# das48.net
KiCad netlist of a schematic drawn in EAGLE
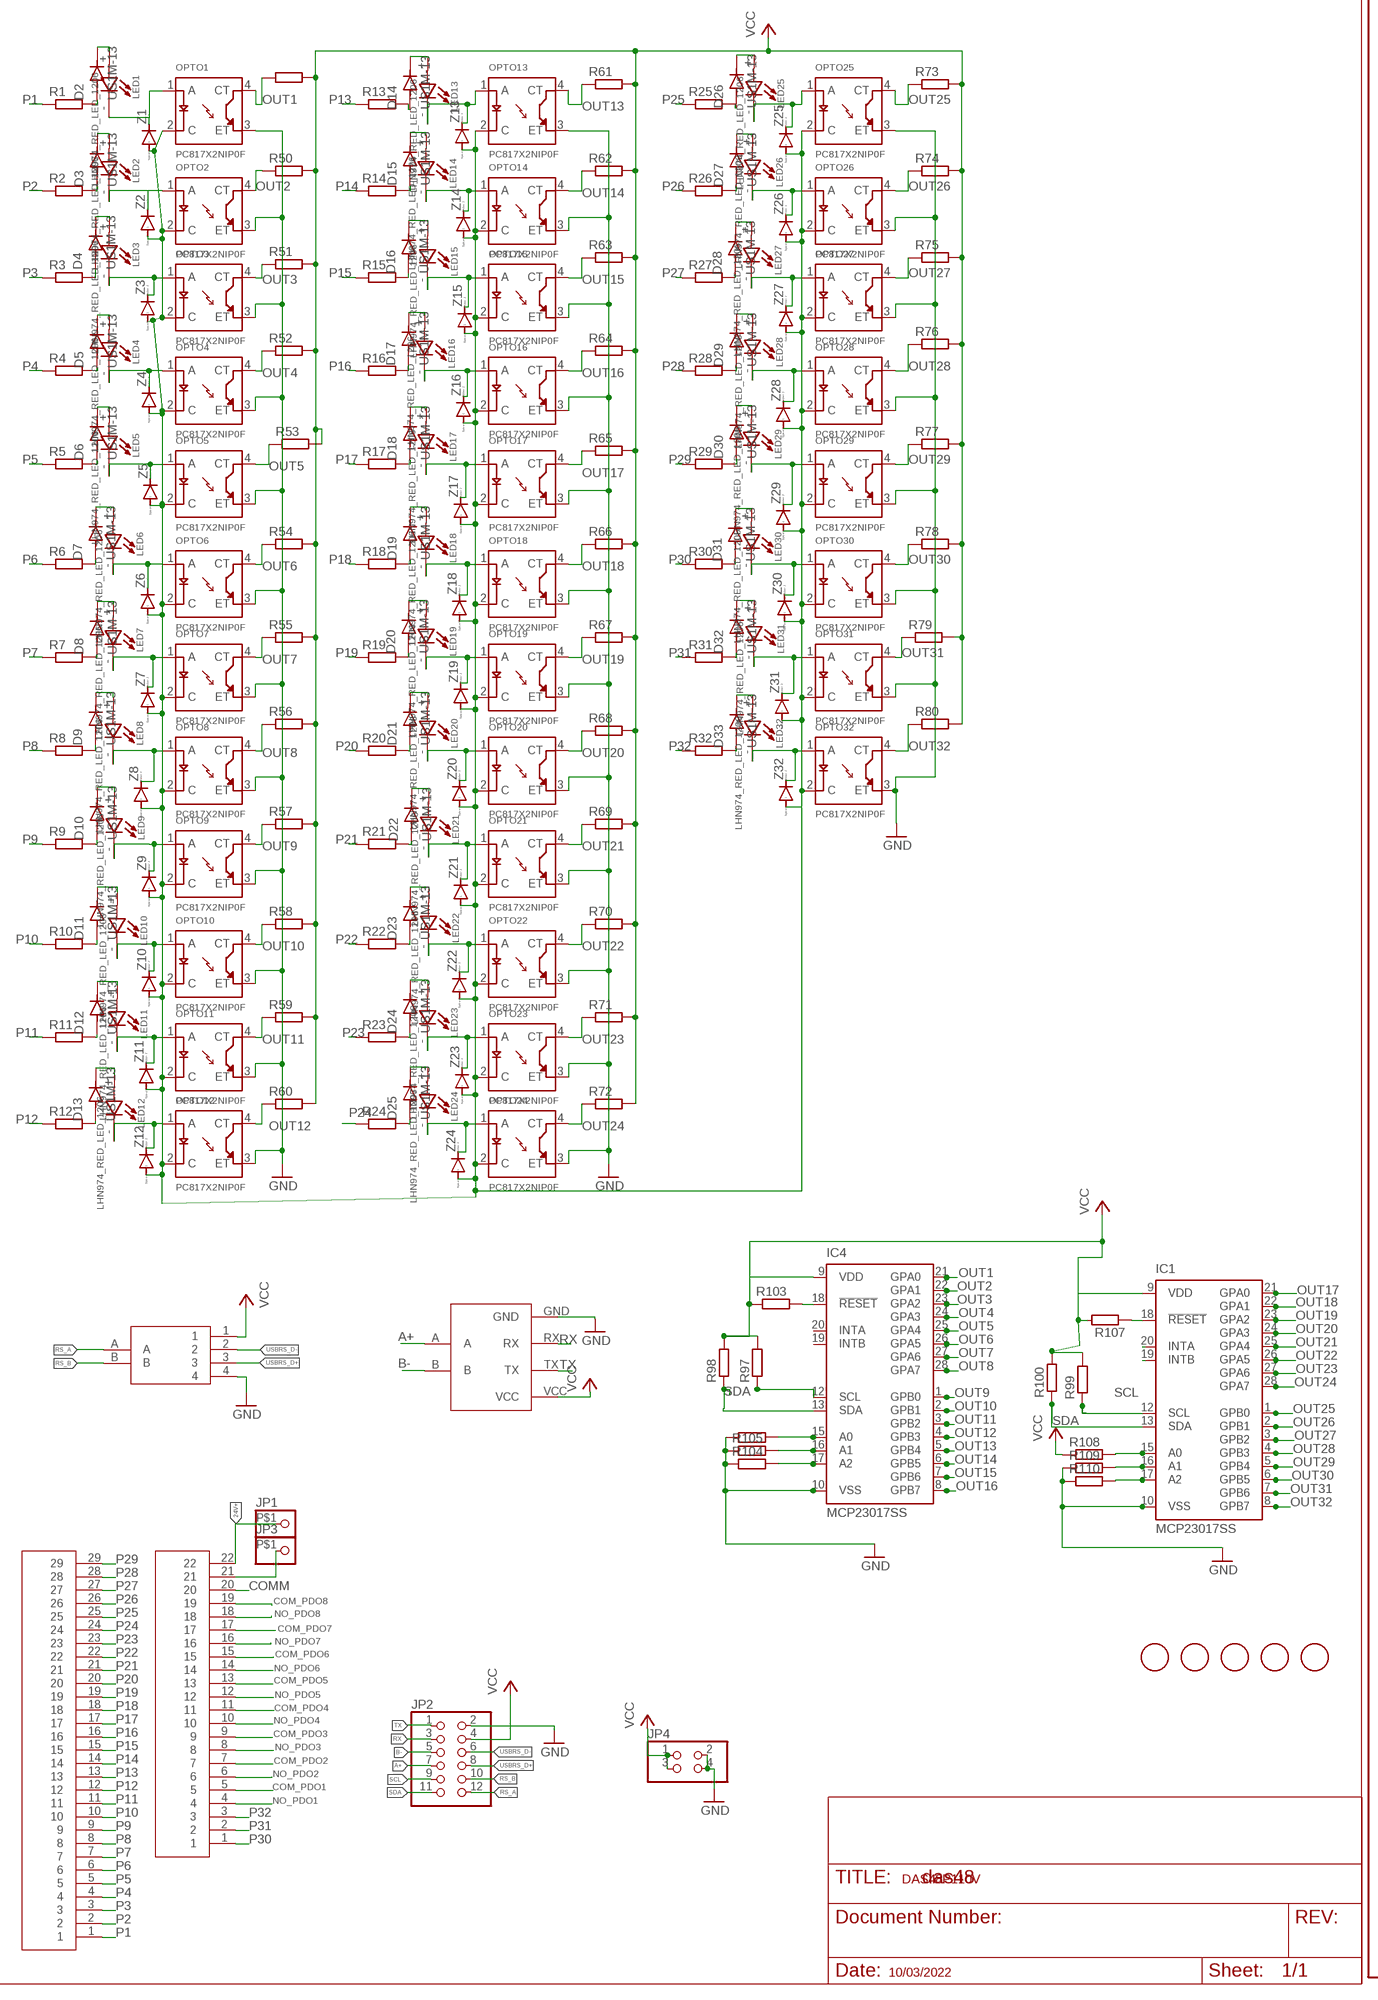
[diagram p0: schematic, sheet 1, part 1 of 2]
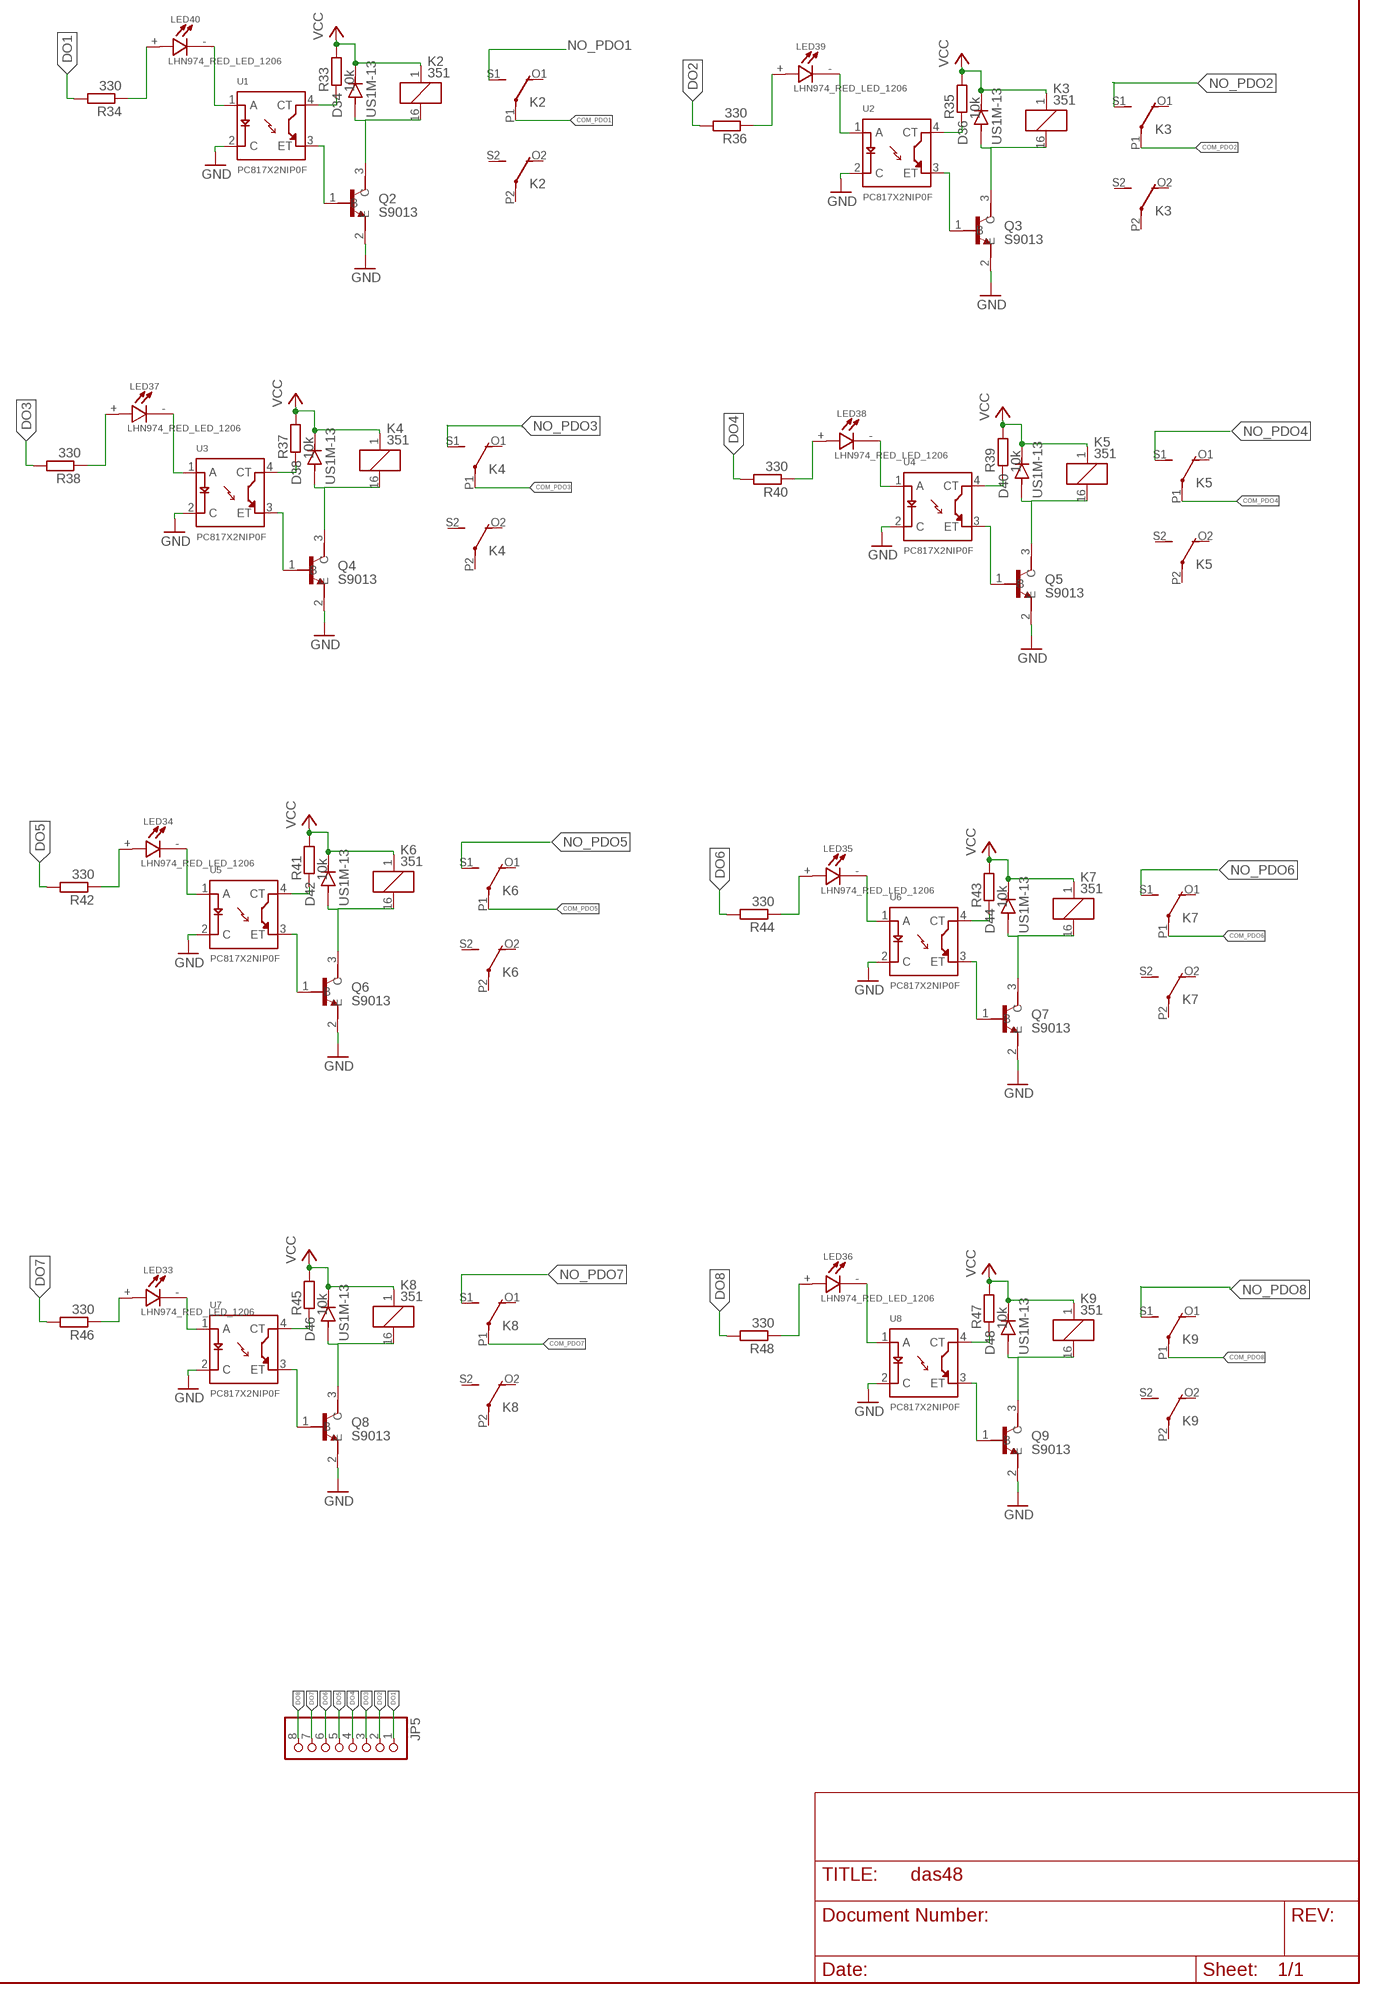
[diagram p1: schematic, sheet 1, part 2 of 2]

(export (version "E")
  (design (tool "Eeschema 10.0.6"))
  (components
    (comp (ref "D2")
      (value "US1M-13")
      (footprint "eagle-import:DIOM5226X240N")
      (fields (field (name "MF") "Diodes Incorporated"))
      (libsource (lib "eagle-import") (part "US1M-13"))
    )
    (comp (ref "D3")
      (value "US1M-13")
      (footprint "eagle-import:DIOM5226X240N")
      (fields (field (name "MF") "Diodes Incorporated"))
      (libsource (lib "eagle-import") (part "US1M-13"))
    )
    (comp (ref "D4")
      (value "US1M-13")
      (footprint "eagle-import:DIOM5226X240N")
      (fields (field (name "MF") "Diodes Incorporated"))
      (libsource (lib "eagle-import") (part "US1M-13"))
    )
    (comp (ref "D5")
      (value "US1M-13")
      (footprint "eagle-import:DIOM5226X240N")
      (fields (field (name "MF") "Diodes Incorporated"))
      (libsource (lib "eagle-import") (part "US1M-13"))
    )
    (comp (ref "D6")
      (value "US1M-13")
      (footprint "eagle-import:DIOM5226X240N")
      (fields (field (name "MF") "Diodes Incorporated"))
      (libsource (lib "eagle-import") (part "US1M-13"))
    )
    (comp (ref "D7")
      (value "US1M-13")
      (footprint "eagle-import:DIOM5226X240N")
      (fields (field (name "MF") "Diodes Incorporated"))
      (libsource (lib "eagle-import") (part "US1M-13"))
    )
    (comp (ref "D8")
      (value "US1M-13")
      (footprint "eagle-import:DIOM5226X240N")
      (fields (field (name "MF") "Diodes Incorporated"))
      (libsource (lib "eagle-import") (part "US1M-13"))
    )
    (comp (ref "D9")
      (value "US1M-13")
      (footprint "eagle-import:DIOM5226X240N")
      (fields (field (name "MF") "Diodes Incorporated"))
      (libsource (lib "eagle-import") (part "US1M-13"))
    )
    (comp (ref "D10")
      (value "US1M-13")
      (footprint "eagle-import:DIOM5226X240N")
      (fields (field (name "MF") "Diodes Incorporated"))
      (libsource (lib "eagle-import") (part "US1M-13"))
    )
    (comp (ref "D11")
      (value "US1M-13")
      (footprint "eagle-import:DIOM5226X240N")
      (fields (field (name "MF") "Diodes Incorporated"))
      (libsource (lib "eagle-import") (part "US1M-13"))
    )
    (comp (ref "D12")
      (value "US1M-13")
      (footprint "eagle-import:DIOM5226X240N")
      (fields (field (name "MF") "Diodes Incorporated"))
      (libsource (lib "eagle-import") (part "US1M-13"))
    )
    (comp (ref "D13")
      (value "US1M-13")
      (footprint "eagle-import:DIOM5226X240N")
      (fields (field (name "MF") "Diodes Incorporated"))
      (libsource (lib "eagle-import") (part "US1M-13"))
    )
    (comp (ref "D14")
      (value "US1M-13")
      (footprint "eagle-import:DIOM5226X240N")
      (fields (field (name "MF") "Diodes Incorporated"))
      (libsource (lib "eagle-import") (part "US1M-13"))
    )
    (comp (ref "D15")
      (value "US1M-13")
      (footprint "eagle-import:DIOM5226X240N")
      (fields (field (name "MF") "Diodes Incorporated"))
      (libsource (lib "eagle-import") (part "US1M-13"))
    )
    (comp (ref "D16")
      (value "US1M-13")
      (footprint "eagle-import:DIOM5226X240N")
      (fields (field (name "MF") "Diodes Incorporated"))
      (libsource (lib "eagle-import") (part "US1M-13"))
    )
    (comp (ref "D17")
      (value "US1M-13")
      (footprint "eagle-import:DIOM5226X240N")
      (fields (field (name "MF") "Diodes Incorporated"))
      (libsource (lib "eagle-import") (part "US1M-13"))
    )
    (comp (ref "D18")
      (value "US1M-13")
      (footprint "eagle-import:DIOM5226X240N")
      (fields (field (name "MF") "Diodes Incorporated"))
      (libsource (lib "eagle-import") (part "US1M-13"))
    )
    (comp (ref "D19")
      (value "US1M-13")
      (footprint "eagle-import:DIOM5226X240N")
      (fields (field (name "MF") "Diodes Incorporated"))
      (libsource (lib "eagle-import") (part "US1M-13"))
    )
    (comp (ref "D20")
      (value "US1M-13")
      (footprint "eagle-import:DIOM5226X240N")
      (fields (field (name "MF") "Diodes Incorporated"))
      (libsource (lib "eagle-import") (part "US1M-13"))
    )
    (comp (ref "D21")
      (value "US1M-13")
      (footprint "eagle-import:DIOM5226X240N")
      (fields (field (name "MF") "Diodes Incorporated"))
      (libsource (lib "eagle-import") (part "US1M-13"))
    )
    (comp (ref "D22")
      (value "US1M-13")
      (footprint "eagle-import:DIOM5226X240N")
      (fields (field (name "MF") "Diodes Incorporated"))
      (libsource (lib "eagle-import") (part "US1M-13"))
    )
    (comp (ref "D23")
      (value "US1M-13")
      (footprint "eagle-import:DIOM5226X240N")
      (fields (field (name "MF") "Diodes Incorporated"))
      (libsource (lib "eagle-import") (part "US1M-13"))
    )
    (comp (ref "D24")
      (value "US1M-13")
      (footprint "eagle-import:DIOM5226X240N")
      (fields (field (name "MF") "Diodes Incorporated"))
      (libsource (lib "eagle-import") (part "US1M-13"))
    )
    (comp (ref "D25")
      (value "US1M-13")
      (footprint "eagle-import:DIOM5226X240N")
      (fields (field (name "MF") "Diodes Incorporated"))
      (libsource (lib "eagle-import") (part "US1M-13"))
    )
    (comp (ref "D26")
      (value "US1M-13")
      (footprint "eagle-import:DIOM5226X240N")
      (fields (field (name "MF") "Diodes Incorporated"))
      (libsource (lib "eagle-import") (part "US1M-13"))
    )
    (comp (ref "D27")
      (value "US1M-13")
      (footprint "eagle-import:DIOM5226X240N")
      (fields (field (name "MF") "Diodes Incorporated"))
      (libsource (lib "eagle-import") (part "US1M-13"))
    )
    (comp (ref "D28")
      (value "US1M-13")
      (footprint "eagle-import:DIOM5226X240N")
      (fields (field (name "MF") "Diodes Incorporated"))
      (libsource (lib "eagle-import") (part "US1M-13"))
    )
    (comp (ref "D29")
      (value "US1M-13")
      (footprint "eagle-import:DIOM5226X240N")
      (fields (field (name "MF") "Diodes Incorporated"))
      (libsource (lib "eagle-import") (part "US1M-13"))
    )
    (comp (ref "D30")
      (value "US1M-13")
      (footprint "eagle-import:DIOM5226X240N")
      (fields (field (name "MF") "Diodes Incorporated"))
      (libsource (lib "eagle-import") (part "US1M-13"))
    )
    (comp (ref "D31")
      (value "US1M-13")
      (footprint "eagle-import:DIOM5226X240N")
      (fields (field (name "MF") "Diodes Incorporated"))
      (libsource (lib "eagle-import") (part "US1M-13"))
    )
    (comp (ref "D32")
      (value "US1M-13")
      (footprint "eagle-import:DIOM5226X240N")
      (fields (field (name "MF") "Diodes Incorporated"))
      (libsource (lib "eagle-import") (part "US1M-13"))
    )
    (comp (ref "D33")
      (value "US1M-13")
      (footprint "eagle-import:DIOM5226X240N")
      (fields (field (name "MF") "Diodes Incorporated"))
      (libsource (lib "eagle-import") (part "US1M-13"))
    )
    (comp (ref "D34")
      (value "US1M-13")
      (footprint "eagle-import:DIOM5226X240N")
      (fields (field (name "MF") "Diodes Incorporated"))
      (libsource (lib "eagle-import") (part "US1M-13"))
    )
    (comp (ref "D36")
      (value "US1M-13")
      (footprint "eagle-import:DIOM5226X240N")
      (fields (field (name "MF") "Diodes Incorporated"))
      (libsource (lib "eagle-import") (part "US1M-13"))
    )
    (comp (ref "D38")
      (value "US1M-13")
      (footprint "eagle-import:DIOM5226X240N")
      (fields (field (name "MF") "Diodes Incorporated"))
      (libsource (lib "eagle-import") (part "US1M-13"))
    )
    (comp (ref "D40")
      (value "US1M-13")
      (footprint "eagle-import:DIOM5226X240N")
      (fields (field (name "MF") "Diodes Incorporated"))
      (libsource (lib "eagle-import") (part "US1M-13"))
    )
    (comp (ref "D42")
      (value "US1M-13")
      (footprint "eagle-import:DIOM5226X240N")
      (fields (field (name "MF") "Diodes Incorporated"))
      (libsource (lib "eagle-import") (part "US1M-13"))
    )
    (comp (ref "D44")
      (value "US1M-13")
      (footprint "eagle-import:DIOM5226X240N")
      (fields (field (name "MF") "Diodes Incorporated"))
      (libsource (lib "eagle-import") (part "US1M-13"))
    )
    (comp (ref "D46")
      (value "US1M-13")
      (footprint "eagle-import:DIOM5226X240N")
      (fields (field (name "MF") "Diodes Incorporated"))
      (libsource (lib "eagle-import") (part "US1M-13"))
    )
    (comp (ref "D48")
      (value "US1M-13")
      (footprint "eagle-import:DIOM5226X240N")
      (fields (field (name "MF") "Diodes Incorporated"))
      (libsource (lib "eagle-import") (part "US1M-13"))
    )
    (comp (ref "HEADER-22P1")
      (value "HEADER-22P")
      (footprint "eagle-import:HEADER-29P")
      (libsource (lib "eagle-import") (part "HEADER-22P"))
    )
    (comp (ref "HEADER-29P1")
      (value "HEADER-29P")
      (footprint "eagle-import:HEADER-29P")
      (libsource (lib "eagle-import") (part "HEADER-29P"))
    )
    (comp (ref "IC1")
      (value "MCP23017SS")
      (footprint "eagle-import:SSOP28DB")
      (libsource (lib "eagle-import") (part "MCP23017SS"))
    )
    (comp (ref "IC4")
      (value "MCP23017SS")
      (footprint "eagle-import:SSOP28DB")
      (libsource (lib "eagle-import") (part "MCP23017SS"))
    )
    (comp (ref "JP1")
      (value "PINHD-1X1-BIGPOGO")
      (footprint "eagle-import:1X1-BIGPOGO")
      (libsource (lib "eagle-import") (part "PINHD-1X1-BIGPOGO"))
    )
    (comp (ref "JP2")
      (value "PINHD-2X6")
      (footprint "eagle-import:2X06")
      (libsource (lib "eagle-import") (part "PINHD-2X6"))
    )
    (comp (ref "JP3")
      (value "PINHD-1X1-BIGPOGO")
      (footprint "eagle-import:1X1-BIGPOGO")
      (libsource (lib "eagle-import") (part "PINHD-1X1-BIGPOGO"))
    )
    (comp (ref "JP4")
      (value "PINHD-2X2")
      (footprint "eagle-import:2X02")
      (libsource (lib "eagle-import") (part "PINHD-2X2"))
    )
    (comp (ref "JP5")
      (value "PINHD-1X8")
      (footprint "eagle-import:1X08")
      (libsource (lib "eagle-import") (part "PINHD-1X8"))
    )
    (comp (ref "K2")
      (value "351")
      (footprint "eagle-import:351")
      (libsource (lib "eagle-import") (part "351"))
    )
    (comp (ref "K3")
      (value "351")
      (footprint "eagle-import:351")
      (libsource (lib "eagle-import") (part "351"))
    )
    (comp (ref "K4")
      (value "351")
      (footprint "eagle-import:351")
      (libsource (lib "eagle-import") (part "351"))
    )
    (comp (ref "K5")
      (value "351")
      (footprint "eagle-import:351")
      (libsource (lib "eagle-import") (part "351"))
    )
    (comp (ref "K6")
      (value "351")
      (footprint "eagle-import:351")
      (libsource (lib "eagle-import") (part "351"))
    )
    (comp (ref "K7")
      (value "351")
      (footprint "eagle-import:351")
      (libsource (lib "eagle-import") (part "351"))
    )
    (comp (ref "K8")
      (value "351")
      (footprint "eagle-import:351")
      (libsource (lib "eagle-import") (part "351"))
    )
    (comp (ref "K9")
      (value "351")
      (footprint "eagle-import:351")
      (libsource (lib "eagle-import") (part "351"))
    )
    (comp (ref "LED1")
      (value "LHN974_RED_LED_1206")
      (footprint "eagle-import:LEDC3216X120N")
      (fields (field (name "MF") "Osram") (field (name "MP") "LHN974 RED LED 1206"))
      (libsource (lib "eagle-import") (part "LHN974_RED_LED_1206"))
    )
    (comp (ref "LED2")
      (value "LHN974_RED_LED_1206")
      (footprint "eagle-import:LEDC3216X120N")
      (fields (field (name "MF") "Osram") (field (name "MP") "LHN974 RED LED 1206"))
      (libsource (lib "eagle-import") (part "LHN974_RED_LED_1206"))
    )
    (comp (ref "LED3")
      (value "LHN974_RED_LED_1206")
      (footprint "eagle-import:LEDC3216X120N")
      (fields (field (name "MF") "Osram") (field (name "MP") "LHN974 RED LED 1206"))
      (libsource (lib "eagle-import") (part "LHN974_RED_LED_1206"))
    )
    (comp (ref "LED4")
      (value "LHN974_RED_LED_1206")
      (footprint "eagle-import:LEDC3216X120N")
      (fields (field (name "MF") "Osram") (field (name "MP") "LHN974 RED LED 1206"))
      (libsource (lib "eagle-import") (part "LHN974_RED_LED_1206"))
    )
    (comp (ref "LED5")
      (value "LHN974_RED_LED_1206")
      (footprint "eagle-import:LEDC3216X120N")
      (fields (field (name "MF") "Osram") (field (name "MP") "LHN974 RED LED 1206"))
      (libsource (lib "eagle-import") (part "LHN974_RED_LED_1206"))
    )
    (comp (ref "LED6")
      (value "LHN974_RED_LED_1206")
      (footprint "eagle-import:LEDC3216X120N")
      (fields (field (name "MF") "Osram") (field (name "MP") "LHN974 RED LED 1206"))
      (libsource (lib "eagle-import") (part "LHN974_RED_LED_1206"))
    )
    (comp (ref "LED7")
      (value "LHN974_RED_LED_1206")
      (footprint "eagle-import:LEDC3216X120N")
      (fields (field (name "MF") "Osram") (field (name "MP") "LHN974 RED LED 1206"))
      (libsource (lib "eagle-import") (part "LHN974_RED_LED_1206"))
    )
    (comp (ref "LED8")
      (value "LHN974_RED_LED_1206")
      (footprint "eagle-import:LEDC3216X120N")
      (fields (field (name "MF") "Osram") (field (name "MP") "LHN974 RED LED 1206"))
      (libsource (lib "eagle-import") (part "LHN974_RED_LED_1206"))
    )
    (comp (ref "LED9")
      (value "LHN974_RED_LED_1206")
      (footprint "eagle-import:LEDC3216X120N")
      (fields (field (name "MF") "Osram") (field (name "MP") "LHN974 RED LED 1206"))
      (libsource (lib "eagle-import") (part "LHN974_RED_LED_1206"))
    )
    (comp (ref "LED10")
      (value "LHN974_RED_LED_1206")
      (footprint "eagle-import:LEDC3216X120N")
      (fields (field (name "MF") "Osram") (field (name "MP") "LHN974 RED LED 1206"))
      (libsource (lib "eagle-import") (part "LHN974_RED_LED_1206"))
    )
    (comp (ref "LED11")
      (value "LHN974_RED_LED_1206")
      (footprint "eagle-import:LEDC3216X120N")
      (fields (field (name "MF") "Osram") (field (name "MP") "LHN974 RED LED 1206"))
      (libsource (lib "eagle-import") (part "LHN974_RED_LED_1206"))
    )
    (comp (ref "LED12")
      (value "LHN974_RED_LED_1206")
      (footprint "eagle-import:LEDC3216X120N")
      (fields (field (name "MF") "Osram") (field (name "MP") "LHN974 RED LED 1206"))
      (libsource (lib "eagle-import") (part "LHN974_RED_LED_1206"))
    )
    (comp (ref "LED13")
      (value "LHN974_RED_LED_1206")
      (footprint "eagle-import:LEDC3216X120N")
      (fields (field (name "MF") "Osram") (field (name "MP") "LHN974 RED LED 1206"))
      (libsource (lib "eagle-import") (part "LHN974_RED_LED_1206"))
    )
    (comp (ref "LED14")
      (value "LHN974_RED_LED_1206")
      (footprint "eagle-import:LEDC3216X120N")
      (fields (field (name "MF") "Osram") (field (name "MP") "LHN974 RED LED 1206"))
      (libsource (lib "eagle-import") (part "LHN974_RED_LED_1206"))
    )
    (comp (ref "LED15")
      (value "LHN974_RED_LED_1206")
      (footprint "eagle-import:LEDC3216X120N")
      (fields (field (name "MF") "Osram") (field (name "MP") "LHN974 RED LED 1206"))
      (libsource (lib "eagle-import") (part "LHN974_RED_LED_1206"))
    )
    (comp (ref "LED16")
      (value "LHN974_RED_LED_1206")
      (footprint "eagle-import:LEDC3216X120N")
      (fields (field (name "MF") "Osram") (field (name "MP") "LHN974 RED LED 1206"))
      (libsource (lib "eagle-import") (part "LHN974_RED_LED_1206"))
    )
    (comp (ref "LED17")
      (value "LHN974_RED_LED_1206")
      (footprint "eagle-import:LEDC3216X120N")
      (fields (field (name "MF") "Osram") (field (name "MP") "LHN974 RED LED 1206"))
      (libsource (lib "eagle-import") (part "LHN974_RED_LED_1206"))
    )
    (comp (ref "LED18")
      (value "LHN974_RED_LED_1206")
      (footprint "eagle-import:LEDC3216X120N")
      (fields (field (name "MF") "Osram") (field (name "MP") "LHN974 RED LED 1206"))
      (libsource (lib "eagle-import") (part "LHN974_RED_LED_1206"))
    )
    (comp (ref "LED19")
      (value "LHN974_RED_LED_1206")
      (footprint "eagle-import:LEDC3216X120N")
      (fields (field (name "MF") "Osram") (field (name "MP") "LHN974 RED LED 1206"))
      (libsource (lib "eagle-import") (part "LHN974_RED_LED_1206"))
    )
    (comp (ref "LED20")
      (value "LHN974_RED_LED_1206")
      (footprint "eagle-import:LEDC3216X120N")
      (fields (field (name "MF") "Osram") (field (name "MP") "LHN974 RED LED 1206"))
      (libsource (lib "eagle-import") (part "LHN974_RED_LED_1206"))
    )
    (comp (ref "LED21")
      (value "LHN974_RED_LED_1206")
      (footprint "eagle-import:LEDC3216X120N")
      (fields (field (name "MF") "Osram") (field (name "MP") "LHN974 RED LED 1206"))
      (libsource (lib "eagle-import") (part "LHN974_RED_LED_1206"))
    )
    (comp (ref "LED22")
      (value "LHN974_RED_LED_1206")
      (footprint "eagle-import:LEDC3216X120N")
      (fields (field (name "MF") "Osram") (field (name "MP") "LHN974 RED LED 1206"))
      (libsource (lib "eagle-import") (part "LHN974_RED_LED_1206"))
    )
    (comp (ref "LED23")
      (value "LHN974_RED_LED_1206")
      (footprint "eagle-import:LEDC3216X120N")
      (fields (field (name "MF") "Osram") (field (name "MP") "LHN974 RED LED 1206"))
      (libsource (lib "eagle-import") (part "LHN974_RED_LED_1206"))
    )
    (comp (ref "LED24")
      (value "LHN974_RED_LED_1206")
      (footprint "eagle-import:LEDC3216X120N")
      (fields (field (name "MF") "Osram") (field (name "MP") "LHN974 RED LED 1206"))
      (libsource (lib "eagle-import") (part "LHN974_RED_LED_1206"))
    )
    (comp (ref "LED25")
      (value "LHN974_RED_LED_1206")
      (footprint "eagle-import:LEDC3216X120N")
      (fields (field (name "MF") "Osram") (field (name "MP") "LHN974 RED LED 1206"))
      (libsource (lib "eagle-import") (part "LHN974_RED_LED_1206"))
    )
    (comp (ref "LED26")
      (value "LHN974_RED_LED_1206")
      (footprint "eagle-import:LEDC3216X120N")
      (fields (field (name "MF") "Osram") (field (name "MP") "LHN974 RED LED 1206"))
      (libsource (lib "eagle-import") (part "LHN974_RED_LED_1206"))
    )
    (comp (ref "LED27")
      (value "LHN974_RED_LED_1206")
      (footprint "eagle-import:LEDC3216X120N")
      (fields (field (name "MF") "Osram") (field (name "MP") "LHN974 RED LED 1206"))
      (libsource (lib "eagle-import") (part "LHN974_RED_LED_1206"))
    )
    (comp (ref "LED28")
      (value "LHN974_RED_LED_1206")
      (footprint "eagle-import:LEDC3216X120N")
      (fields (field (name "MF") "Osram") (field (name "MP") "LHN974 RED LED 1206"))
      (libsource (lib "eagle-import") (part "LHN974_RED_LED_1206"))
    )
    (comp (ref "LED29")
      (value "LHN974_RED_LED_1206")
      (footprint "eagle-import:LEDC3216X120N")
      (fields (field (name "MF") "Osram") (field (name "MP") "LHN974 RED LED 1206"))
      (libsource (lib "eagle-import") (part "LHN974_RED_LED_1206"))
    )
    (comp (ref "LED30")
      (value "LHN974_RED_LED_1206")
      (footprint "eagle-import:LEDC3216X120N")
      (fields (field (name "MF") "Osram") (field (name "MP") "LHN974 RED LED 1206"))
      (libsource (lib "eagle-import") (part "LHN974_RED_LED_1206"))
    )
    (comp (ref "LED31")
      (value "LHN974_RED_LED_1206")
      (footprint "eagle-import:LEDC3216X120N")
      (fields (field (name "MF") "Osram") (field (name "MP") "LHN974 RED LED 1206"))
      (libsource (lib "eagle-import") (part "LHN974_RED_LED_1206"))
    )
    (comp (ref "LED32")
      (value "LHN974_RED_LED_1206")
      (footprint "eagle-import:LEDC3216X120N")
      (fields (field (name "MF") "Osram") (field (name "MP") "LHN974 RED LED 1206"))
      (libsource (lib "eagle-import") (part "LHN974_RED_LED_1206"))
    )
    (comp (ref "LED33")
      (value "LHN974_RED_LED_1206")
      (footprint "eagle-import:LEDC3216X120N")
      (fields (field (name "MF") "Osram") (field (name "MP") "LHN974 RED LED 1206"))
      (libsource (lib "eagle-import") (part "LHN974_RED_LED_1206"))
    )
    (comp (ref "LED34")
      (value "LHN974_RED_LED_1206")
      (footprint "eagle-import:LEDC3216X120N")
      (fields (field (name "MF") "Osram") (field (name "MP") "LHN974 RED LED 1206"))
      (libsource (lib "eagle-import") (part "LHN974_RED_LED_1206"))
    )
    (comp (ref "LED35")
      (value "LHN974_RED_LED_1206")
      (footprint "eagle-import:LEDC3216X120N")
      (fields (field (name "MF") "Osram") (field (name "MP") "LHN974 RED LED 1206"))
      (libsource (lib "eagle-import") (part "LHN974_RED_LED_1206"))
    )
    (comp (ref "LED36")
      (value "LHN974_RED_LED_1206")
      (footprint "eagle-import:LEDC3216X120N")
      (fields (field (name "MF") "Osram") (field (name "MP") "LHN974 RED LED 1206"))
      (libsource (lib "eagle-import") (part "LHN974_RED_LED_1206"))
    )
    (comp (ref "LED37")
      (value "LHN974_RED_LED_1206")
      (footprint "eagle-import:LEDC3216X120N")
      (fields (field (name "MF") "Osram") (field (name "MP") "LHN974 RED LED 1206"))
      (libsource (lib "eagle-import") (part "LHN974_RED_LED_1206"))
    )
    (comp (ref "LED38")
      (value "LHN974_RED_LED_1206")
      (footprint "eagle-import:LEDC3216X120N")
      (fields (field (name "MF") "Osram") (field (name "MP") "LHN974 RED LED 1206"))
      (libsource (lib "eagle-import") (part "LHN974_RED_LED_1206"))
    )
    (comp (ref "LED39")
      (value "LHN974_RED_LED_1206")
      (footprint "eagle-import:LEDC3216X120N")
      (fields (field (name "MF") "Osram") (field (name "MP") "LHN974 RED LED 1206"))
      (libsource (lib "eagle-import") (part "LHN974_RED_LED_1206"))
    )
    (comp (ref "LED40")
      (value "LHN974_RED_LED_1206")
      (footprint "eagle-import:LEDC3216X120N")
      (fields (field (name "MF") "Osram") (field (name "MP") "LHN974 RED LED 1206"))
      (libsource (lib "eagle-import") (part "LHN974_RED_LED_1206"))
    )
    (comp (ref "OPTO1")
      (value "PC817X2NIP0F")
      (footprint "eagle-import:SOT254P975X400-4N")
      (fields (field (name "MF") "Sharp Microelectronics"))
      (libsource (lib "eagle-import") (part "PC817X2NIP0F"))
    )
    (comp (ref "OPTO2")
      (value "PC817X2NIP0F")
      (footprint "eagle-import:SOT254P975X400-4N")
      (fields (field (name "MF") "Sharp Microelectronics"))
      (libsource (lib "eagle-import") (part "PC817X2NIP0F"))
    )
    (comp (ref "OPTO3")
      (value "PC817X2NIP0F")
      (footprint "eagle-import:SOT254P975X400-4N")
      (fields (field (name "MF") "Sharp Microelectronics"))
      (libsource (lib "eagle-import") (part "PC817X2NIP0F"))
    )
    (comp (ref "OPTO4")
      (value "PC817X2NIP0F")
      (footprint "eagle-import:SOT254P975X400-4N")
      (fields (field (name "MF") "Sharp Microelectronics"))
      (libsource (lib "eagle-import") (part "PC817X2NIP0F"))
    )
    (comp (ref "OPTO5")
      (value "PC817X2NIP0F")
      (footprint "eagle-import:SOT254P975X400-4N")
      (fields (field (name "MF") "Sharp Microelectronics"))
      (libsource (lib "eagle-import") (part "PC817X2NIP0F"))
    )
    (comp (ref "OPTO6")
      (value "PC817X2NIP0F")
      (footprint "eagle-import:SOT254P975X400-4N")
      (fields (field (name "MF") "Sharp Microelectronics"))
      (libsource (lib "eagle-import") (part "PC817X2NIP0F"))
    )
    (comp (ref "OPTO7")
      (value "PC817X2NIP0F")
      (footprint "eagle-import:SOT254P975X400-4N")
      (fields (field (name "MF") "Sharp Microelectronics"))
      (libsource (lib "eagle-import") (part "PC817X2NIP0F"))
    )
    (comp (ref "OPTO8")
      (value "PC817X2NIP0F")
      (footprint "eagle-import:SOT254P975X400-4N")
      (fields (field (name "MF") "Sharp Microelectronics"))
      (libsource (lib "eagle-import") (part "PC817X2NIP0F"))
    )
    (comp (ref "OPTO9")
      (value "PC817X2NIP0F")
      (footprint "eagle-import:SOT254P975X400-4N")
      (fields (field (name "MF") "Sharp Microelectronics"))
      (libsource (lib "eagle-import") (part "PC817X2NIP0F"))
    )
    (comp (ref "OPTO10")
      (value "PC817X2NIP0F")
      (footprint "eagle-import:SOT254P975X400-4N")
      (fields (field (name "MF") "Sharp Microelectronics"))
      (libsource (lib "eagle-import") (part "PC817X2NIP0F"))
    )
    (comp (ref "OPTO11")
      (value "PC817X2NIP0F")
      (footprint "eagle-import:SOT254P975X400-4N")
      (fields (field (name "MF") "Sharp Microelectronics"))
      (libsource (lib "eagle-import") (part "PC817X2NIP0F"))
    )
    (comp (ref "OPTO12")
      (value "PC817X2NIP0F")
      (footprint "eagle-import:SOT254P975X400-4N")
      (fields (field (name "MF") "Sharp Microelectronics"))
      (libsource (lib "eagle-import") (part "PC817X2NIP0F"))
    )
    (comp (ref "OPTO13")
      (value "PC817X2NIP0F")
      (footprint "eagle-import:SOT254P975X400-4N")
      (fields (field (name "MF") "Sharp Microelectronics"))
      (libsource (lib "eagle-import") (part "PC817X2NIP0F"))
    )
    (comp (ref "OPTO14")
      (value "PC817X2NIP0F")
      (footprint "eagle-import:SOT254P975X400-4N")
      (fields (field (name "MF") "Sharp Microelectronics"))
      (libsource (lib "eagle-import") (part "PC817X2NIP0F"))
    )
    (comp (ref "OPTO15")
      (value "PC817X2NIP0F")
      (footprint "eagle-import:SOT254P975X400-4N")
      (fields (field (name "MF") "Sharp Microelectronics"))
      (libsource (lib "eagle-import") (part "PC817X2NIP0F"))
    )
    (comp (ref "OPTO16")
      (value "PC817X2NIP0F")
      (footprint "eagle-import:SOT254P975X400-4N")
      (fields (field (name "MF") "Sharp Microelectronics"))
      (libsource (lib "eagle-import") (part "PC817X2NIP0F"))
    )
    (comp (ref "OPTO17")
      (value "PC817X2NIP0F")
      (footprint "eagle-import:SOT254P975X400-4N")
      (fields (field (name "MF") "Sharp Microelectronics"))
      (libsource (lib "eagle-import") (part "PC817X2NIP0F"))
    )
    (comp (ref "OPTO18")
      (value "PC817X2NIP0F")
      (footprint "eagle-import:SOT254P975X400-4N")
      (fields (field (name "MF") "Sharp Microelectronics"))
      (libsource (lib "eagle-import") (part "PC817X2NIP0F"))
    )
    (comp (ref "OPTO19")
      (value "PC817X2NIP0F")
      (footprint "eagle-import:SOT254P975X400-4N")
      (fields (field (name "MF") "Sharp Microelectronics"))
      (libsource (lib "eagle-import") (part "PC817X2NIP0F"))
    )
    (comp (ref "OPTO20")
      (value "PC817X2NIP0F")
      (footprint "eagle-import:SOT254P975X400-4N")
      (fields (field (name "MF") "Sharp Microelectronics"))
      (libsource (lib "eagle-import") (part "PC817X2NIP0F"))
    )
    (comp (ref "OPTO21")
      (value "PC817X2NIP0F")
      (footprint "eagle-import:SOT254P975X400-4N")
      (fields (field (name "MF") "Sharp Microelectronics"))
      (libsource (lib "eagle-import") (part "PC817X2NIP0F"))
    )
    (comp (ref "OPTO22")
      (value "PC817X2NIP0F")
      (footprint "eagle-import:SOT254P975X400-4N")
      (fields (field (name "MF") "Sharp Microelectronics"))
      (libsource (lib "eagle-import") (part "PC817X2NIP0F"))
    )
    (comp (ref "OPTO23")
      (value "PC817X2NIP0F")
      (footprint "eagle-import:SOT254P975X400-4N")
      (fields (field (name "MF") "Sharp Microelectronics"))
      (libsource (lib "eagle-import") (part "PC817X2NIP0F"))
    )
    (comp (ref "OPTO24")
      (value "PC817X2NIP0F")
      (footprint "eagle-import:SOT254P975X400-4N")
      (fields (field (name "MF") "Sharp Microelectronics"))
      (libsource (lib "eagle-import") (part "PC817X2NIP0F"))
    )
    (comp (ref "OPTO25")
      (value "PC817X2NIP0F")
      (footprint "eagle-import:SOT254P975X400-4N")
      (fields (field (name "MF") "Sharp Microelectronics"))
      (libsource (lib "eagle-import") (part "PC817X2NIP0F"))
    )
    (comp (ref "OPTO26")
      (value "PC817X2NIP0F")
      (footprint "eagle-import:SOT254P975X400-4N")
      (fields (field (name "MF") "Sharp Microelectronics"))
      (libsource (lib "eagle-import") (part "PC817X2NIP0F"))
    )
    (comp (ref "OPTO27")
      (value "PC817X2NIP0F")
      (footprint "eagle-import:SOT254P975X400-4N")
      (fields (field (name "MF") "Sharp Microelectronics"))
      (libsource (lib "eagle-import") (part "PC817X2NIP0F"))
    )
    (comp (ref "OPTO28")
      (value "PC817X2NIP0F")
      (footprint "eagle-import:SOT254P975X400-4N")
      (fields (field (name "MF") "Sharp Microelectronics"))
      (libsource (lib "eagle-import") (part "PC817X2NIP0F"))
    )
    (comp (ref "OPTO29")
      (value "PC817X2NIP0F")
      (footprint "eagle-import:SOT254P975X400-4N")
      (fields (field (name "MF") "Sharp Microelectronics"))
      (libsource (lib "eagle-import") (part "PC817X2NIP0F"))
    )
    (comp (ref "OPTO30")
      (value "PC817X2NIP0F")
      (footprint "eagle-import:SOT254P975X400-4N")
      (fields (field (name "MF") "Sharp Microelectronics"))
      (libsource (lib "eagle-import") (part "PC817X2NIP0F"))
    )
    (comp (ref "OPTO31")
      (value "PC817X2NIP0F")
      (footprint "eagle-import:SOT254P975X400-4N")
      (fields (field (name "MF") "Sharp Microelectronics"))
      (libsource (lib "eagle-import") (part "PC817X2NIP0F"))
    )
    (comp (ref "OPTO32")
      (value "PC817X2NIP0F")
      (footprint "eagle-import:SOT254P975X400-4N")
      (fields (field (name "MF") "Sharp Microelectronics"))
      (libsource (lib "eagle-import") (part "PC817X2NIP0F"))
    )
    (comp (ref "Q2")
      (value "S9013")
      (footprint "eagle-import:SOT95P240X120-3N")
      (fields (field (name "MF") "JCET"))
      (libsource (lib "eagle-import") (part "S9013"))
    )
    (comp (ref "Q3")
      (value "S9013")
      (footprint "eagle-import:SOT95P240X120-3N")
      (fields (field (name "MF") "JCET"))
      (libsource (lib "eagle-import") (part "S9013"))
    )
    (comp (ref "Q4")
      (value "S9013")
      (footprint "eagle-import:SOT95P240X120-3N")
      (fields (field (name "MF") "JCET"))
      (libsource (lib "eagle-import") (part "S9013"))
    )
    (comp (ref "Q5")
      (value "S9013")
      (footprint "eagle-import:SOT95P240X120-3N")
      (fields (field (name "MF") "JCET"))
      (libsource (lib "eagle-import") (part "S9013"))
    )
    (comp (ref "Q6")
      (value "S9013")
      (footprint "eagle-import:SOT95P240X120-3N")
      (fields (field (name "MF") "JCET"))
      (libsource (lib "eagle-import") (part "S9013"))
    )
    (comp (ref "Q7")
      (value "S9013")
      (footprint "eagle-import:SOT95P240X120-3N")
      (fields (field (name "MF") "JCET"))
      (libsource (lib "eagle-import") (part "S9013"))
    )
    (comp (ref "Q8")
      (value "S9013")
      (footprint "eagle-import:SOT95P240X120-3N")
      (fields (field (name "MF") "JCET"))
      (libsource (lib "eagle-import") (part "S9013"))
    )
    (comp (ref "Q9")
      (value "S9013")
      (footprint "eagle-import:SOT95P240X120-3N")
      (fields (field (name "MF") "JCET"))
      (libsource (lib "eagle-import") (part "S9013"))
    )
    (comp (ref "R1")
      (value "R-EU_0617/17")
      (footprint "eagle-import:0617_17")
      (libsource (lib "eagle-import") (part "R-EU_0617/17"))
    )
    (comp (ref "R2")
      (value "R-EU_0617/17")
      (footprint "eagle-import:0617_17")
      (libsource (lib "eagle-import") (part "R-EU_0617/17"))
    )
    (comp (ref "R3")
      (value "R-EU_0617/17")
      (footprint "eagle-import:0617_17")
      (libsource (lib "eagle-import") (part "R-EU_0617/17"))
    )
    (comp (ref "R4")
      (value "R-EU_0617/17")
      (footprint "eagle-import:0617_17")
      (libsource (lib "eagle-import") (part "R-EU_0617/17"))
    )
    (comp (ref "R5")
      (value "R-EU_0617/17")
      (footprint "eagle-import:0617_17")
      (libsource (lib "eagle-import") (part "R-EU_0617/17"))
    )
    (comp (ref "R6")
      (value "R-EU_0617/17")
      (footprint "eagle-import:0617_17")
      (libsource (lib "eagle-import") (part "R-EU_0617/17"))
    )
    (comp (ref "R7")
      (value "R-EU_0617/17")
      (footprint "eagle-import:0617_17")
      (libsource (lib "eagle-import") (part "R-EU_0617/17"))
    )
    (comp (ref "R8")
      (value "R-EU_0617/17")
      (footprint "eagle-import:0617_17")
      (libsource (lib "eagle-import") (part "R-EU_0617/17"))
    )
    (comp (ref "R9")
      (value "R-EU_0617/17")
      (footprint "eagle-import:0617_17")
      (libsource (lib "eagle-import") (part "R-EU_0617/17"))
    )
    (comp (ref "R10")
      (value "R-EU_0617/17")
      (footprint "eagle-import:0617_17")
      (libsource (lib "eagle-import") (part "R-EU_0617/17"))
    )
    (comp (ref "R11")
      (value "R-EU_0617/17")
      (footprint "eagle-import:0617_17")
      (libsource (lib "eagle-import") (part "R-EU_0617/17"))
    )
    (comp (ref "R12")
      (value "R-EU_0617/17")
      (footprint "eagle-import:0617_17")
      (libsource (lib "eagle-import") (part "R-EU_0617/17"))
    )
    (comp (ref "R13")
      (value "R-EU_0617/17")
      (footprint "eagle-import:0617_17")
      (libsource (lib "eagle-import") (part "R-EU_0617/17"))
    )
    (comp (ref "R14")
      (value "R-EU_0617/17")
      (footprint "eagle-import:0617_17")
      (libsource (lib "eagle-import") (part "R-EU_0617/17"))
    )
    (comp (ref "R15")
      (value "R-EU_0617/17")
      (footprint "eagle-import:0617_17")
      (libsource (lib "eagle-import") (part "R-EU_0617/17"))
    )
    (comp (ref "R16")
      (value "R-EU_0617/17")
      (footprint "eagle-import:0617_17")
      (libsource (lib "eagle-import") (part "R-EU_0617/17"))
    )
    (comp (ref "R17")
      (value "R-EU_0617/17")
      (footprint "eagle-import:0617_17")
      (libsource (lib "eagle-import") (part "R-EU_0617/17"))
    )
    (comp (ref "R18")
      (value "R-EU_0617/17")
      (footprint "eagle-import:0617_17")
      (libsource (lib "eagle-import") (part "R-EU_0617/17"))
    )
    (comp (ref "R19")
      (value "R-EU_0617/17")
      (footprint "eagle-import:0617_17")
      (libsource (lib "eagle-import") (part "R-EU_0617/17"))
    )
    (comp (ref "R20")
      (value "R-EU_0617/17")
      (footprint "eagle-import:0617_17")
      (libsource (lib "eagle-import") (part "R-EU_0617/17"))
    )
    (comp (ref "R21")
      (value "R-EU_0617/17")
      (footprint "eagle-import:0617_17")
      (libsource (lib "eagle-import") (part "R-EU_0617/17"))
    )
    (comp (ref "R22")
      (value "R-EU_0617/17")
      (footprint "eagle-import:0617_17")
      (libsource (lib "eagle-import") (part "R-EU_0617/17"))
    )
    (comp (ref "R23")
      (value "R-EU_0617/17")
      (footprint "eagle-import:0617_17")
      (libsource (lib "eagle-import") (part "R-EU_0617/17"))
    )
    (comp (ref "R24")
      (value "R-EU_0617/17")
      (footprint "eagle-import:0617_17")
      (libsource (lib "eagle-import") (part "R-EU_0617/17"))
    )
    (comp (ref "R25")
      (value "R-EU_0617/17")
      (footprint "eagle-import:0617_17")
      (libsource (lib "eagle-import") (part "R-EU_0617/17"))
    )
    (comp (ref "R26")
      (value "R-EU_0617/17")
      (footprint "eagle-import:0617_17")
      (libsource (lib "eagle-import") (part "R-EU_0617/17"))
    )
    (comp (ref "R27")
      (value "R-EU_0617/17")
      (footprint "eagle-import:0617_17")
      (libsource (lib "eagle-import") (part "R-EU_0617/17"))
    )
    (comp (ref "R28")
      (value "R-EU_0617/17")
      (footprint "eagle-import:0617_17")
      (libsource (lib "eagle-import") (part "R-EU_0617/17"))
    )
    (comp (ref "R29")
      (value "R-EU_0617/17")
      (footprint "eagle-import:0617_17")
      (libsource (lib "eagle-import") (part "R-EU_0617/17"))
    )
    (comp (ref "R30")
      (value "R-EU_0617/17")
      (footprint "eagle-import:0617_17")
      (libsource (lib "eagle-import") (part "R-EU_0617/17"))
    )
    (comp (ref "R31")
      (value "R-EU_0617/17")
      (footprint "eagle-import:0617_17")
      (libsource (lib "eagle-import") (part "R-EU_0617/17"))
    )
    (comp (ref "R32")
      (value "R-EU_0617/17")
      (footprint "eagle-import:0617_17")
      (libsource (lib "eagle-import") (part "R-EU_0617/17"))
    )
    (comp (ref "R33")
      (value "10k")
      (footprint "eagle-import:R0805")
      (libsource (lib "eagle-import") (part "R-EU_R0805"))
    )
    (comp (ref "R34")
      (value "330")
      (footprint "eagle-import:R0805")
      (libsource (lib "eagle-import") (part "R-EU_R0805"))
    )
    (comp (ref "R35")
      (value "10k")
      (footprint "eagle-import:R0805")
      (libsource (lib "eagle-import") (part "R-EU_R0805"))
    )
    (comp (ref "R36")
      (value "330")
      (footprint "eagle-import:R0805")
      (libsource (lib "eagle-import") (part "R-EU_R0805"))
    )
    (comp (ref "R37")
      (value "10k")
      (footprint "eagle-import:R0805")
      (libsource (lib "eagle-import") (part "R-EU_R0805"))
    )
    (comp (ref "R38")
      (value "330")
      (footprint "eagle-import:R0805")
      (libsource (lib "eagle-import") (part "R-EU_R0805"))
    )
    (comp (ref "R39")
      (value "10k")
      (footprint "eagle-import:R0805")
      (libsource (lib "eagle-import") (part "R-EU_R0805"))
    )
    (comp (ref "R40")
      (value "330")
      (footprint "eagle-import:R0805")
      (libsource (lib "eagle-import") (part "R-EU_R0805"))
    )
    (comp (ref "R41")
      (value "10k")
      (footprint "eagle-import:R0805")
      (libsource (lib "eagle-import") (part "R-EU_R0805"))
    )
    (comp (ref "R42")
      (value "330")
      (footprint "eagle-import:R0805")
      (libsource (lib "eagle-import") (part "R-EU_R0805"))
    )
    (comp (ref "R43")
      (value "10k")
      (footprint "eagle-import:R0805")
      (libsource (lib "eagle-import") (part "R-EU_R0805"))
    )
    (comp (ref "R44")
      (value "330")
      (footprint "eagle-import:R0805")
      (libsource (lib "eagle-import") (part "R-EU_R0805"))
    )
    (comp (ref "R45")
      (value "10k")
      (footprint "eagle-import:R0805")
      (libsource (lib "eagle-import") (part "R-EU_R0805"))
    )
    (comp (ref "R46")
      (value "330")
      (footprint "eagle-import:R0805")
      (libsource (lib "eagle-import") (part "R-EU_R0805"))
    )
    (comp (ref "R47")
      (value "10k")
      (footprint "eagle-import:R0805")
      (libsource (lib "eagle-import") (part "R-EU_R0805"))
    )
    (comp (ref "R48")
      (value "330")
      (footprint "eagle-import:R0805")
      (libsource (lib "eagle-import") (part "R-EU_R0805"))
    )
    (comp (ref "R49")
      (value "R-EU_R0805")
      (footprint "eagle-import:R0805")
      (libsource (lib "eagle-import") (part "R-EU_R0805"))
    )
    (comp (ref "R50")
      (value "R-EU_R0805")
      (footprint "eagle-import:R0805")
      (libsource (lib "eagle-import") (part "R-EU_R0805"))
    )
    (comp (ref "R51")
      (value "R-EU_R0805")
      (footprint "eagle-import:R0805")
      (libsource (lib "eagle-import") (part "R-EU_R0805"))
    )
    (comp (ref "R52")
      (value "R-EU_R0805")
      (footprint "eagle-import:R0805")
      (libsource (lib "eagle-import") (part "R-EU_R0805"))
    )
    (comp (ref "R53")
      (value "R-EU_R0805")
      (footprint "eagle-import:R0805")
      (libsource (lib "eagle-import") (part "R-EU_R0805"))
    )
    (comp (ref "R54")
      (value "R-EU_R0805")
      (footprint "eagle-import:R0805")
      (libsource (lib "eagle-import") (part "R-EU_R0805"))
    )
    (comp (ref "R55")
      (value "R-EU_R0805")
      (footprint "eagle-import:R0805")
      (libsource (lib "eagle-import") (part "R-EU_R0805"))
    )
    (comp (ref "R56")
      (value "R-EU_R0805")
      (footprint "eagle-import:R0805")
      (libsource (lib "eagle-import") (part "R-EU_R0805"))
    )
    (comp (ref "R57")
      (value "R-EU_R0805")
      (footprint "eagle-import:R0805")
      (libsource (lib "eagle-import") (part "R-EU_R0805"))
    )
    (comp (ref "R58")
      (value "R-EU_R0805")
      (footprint "eagle-import:R0805")
      (libsource (lib "eagle-import") (part "R-EU_R0805"))
    )
    (comp (ref "R59")
      (value "R-EU_R0805")
      (footprint "eagle-import:R0805")
      (libsource (lib "eagle-import") (part "R-EU_R0805"))
    )
    (comp (ref "R60")
      (value "R-EU_R0805")
      (footprint "eagle-import:R0805")
      (libsource (lib "eagle-import") (part "R-EU_R0805"))
    )
    (comp (ref "R61")
      (value "R-EU_R0805")
      (footprint "eagle-import:R0805")
      (libsource (lib "eagle-import") (part "R-EU_R0805"))
    )
    (comp (ref "R62")
      (value "R-EU_R0805")
      (footprint "eagle-import:R0805")
      (libsource (lib "eagle-import") (part "R-EU_R0805"))
    )
    (comp (ref "R63")
      (value "R-EU_R0805")
      (footprint "eagle-import:R0805")
      (libsource (lib "eagle-import") (part "R-EU_R0805"))
    )
    (comp (ref "R64")
      (value "R-EU_R0805")
      (footprint "eagle-import:R0805")
      (libsource (lib "eagle-import") (part "R-EU_R0805"))
    )
    (comp (ref "R65")
      (value "R-EU_R0805")
      (footprint "eagle-import:R0805")
      (libsource (lib "eagle-import") (part "R-EU_R0805"))
    )
    (comp (ref "R66")
      (value "R-EU_R0805")
      (footprint "eagle-import:R0805")
      (libsource (lib "eagle-import") (part "R-EU_R0805"))
    )
    (comp (ref "R67")
      (value "R-EU_R0805")
      (footprint "eagle-import:R0805")
      (libsource (lib "eagle-import") (part "R-EU_R0805"))
    )
    (comp (ref "R68")
      (value "R-EU_R0805")
      (footprint "eagle-import:R0805")
      (libsource (lib "eagle-import") (part "R-EU_R0805"))
    )
    (comp (ref "R69")
      (value "R-EU_R0805")
      (footprint "eagle-import:R0805")
      (libsource (lib "eagle-import") (part "R-EU_R0805"))
    )
    (comp (ref "R70")
      (value "R-EU_R0805")
      (footprint "eagle-import:R0805")
      (libsource (lib "eagle-import") (part "R-EU_R0805"))
    )
    (comp (ref "R71")
      (value "R-EU_R0805")
      (footprint "eagle-import:R0805")
      (libsource (lib "eagle-import") (part "R-EU_R0805"))
    )
    (comp (ref "R72")
      (value "R-EU_R0805")
      (footprint "eagle-import:R0805")
      (libsource (lib "eagle-import") (part "R-EU_R0805"))
    )
    (comp (ref "R73")
      (value "R-EU_R0805")
      (footprint "eagle-import:R0805")
      (libsource (lib "eagle-import") (part "R-EU_R0805"))
    )
    (comp (ref "R74")
      (value "R-EU_R0805")
      (footprint "eagle-import:R0805")
      (libsource (lib "eagle-import") (part "R-EU_R0805"))
    )
    (comp (ref "R75")
      (value "R-EU_R0805")
      (footprint "eagle-import:R0805")
      (libsource (lib "eagle-import") (part "R-EU_R0805"))
    )
    (comp (ref "R76")
      (value "R-EU_R0805")
      (footprint "eagle-import:R0805")
      (libsource (lib "eagle-import") (part "R-EU_R0805"))
    )
    (comp (ref "R77")
      (value "R-EU_R0805")
      (footprint "eagle-import:R0805")
      (libsource (lib "eagle-import") (part "R-EU_R0805"))
    )
    (comp (ref "R78")
      (value "R-EU_R0805")
      (footprint "eagle-import:R0805")
      (libsource (lib "eagle-import") (part "R-EU_R0805"))
    )
    (comp (ref "R79")
      (value "R-EU_R0805")
      (footprint "eagle-import:R0805")
      (libsource (lib "eagle-import") (part "R-EU_R0805"))
    )
    (comp (ref "R80")
      (value "R-EU_R0805")
      (footprint "eagle-import:R0805")
      (libsource (lib "eagle-import") (part "R-EU_R0805"))
    )
    (comp (ref "R97")
      (value "R-EU_R0805")
      (footprint "eagle-import:R0805")
      (libsource (lib "eagle-import") (part "R-EU_R0805"))
    )
    (comp (ref "R98")
      (value "R-EU_R0805")
      (footprint "eagle-import:R0805")
      (libsource (lib "eagle-import") (part "R-EU_R0805"))
    )
    (comp (ref "R99")
      (value "R-EU_R0805")
      (footprint "eagle-import:R0805")
      (libsource (lib "eagle-import") (part "R-EU_R0805"))
    )
    (comp (ref "R100")
      (value "R-EU_R0805")
      (footprint "eagle-import:R0805")
      (libsource (lib "eagle-import") (part "R-EU_R0805"))
    )
    (comp (ref "R103")
      (value "R-EU_R0805")
      (footprint "eagle-import:R0805")
      (libsource (lib "eagle-import") (part "R-EU_R0805"))
    )
    (comp (ref "R104")
      (value "R-EU_R0805")
      (footprint "eagle-import:R0805")
      (libsource (lib "eagle-import") (part "R-EU_R0805"))
    )
    (comp (ref "R105")
      (value "R-EU_R0805")
      (footprint "eagle-import:R0805")
      (libsource (lib "eagle-import") (part "R-EU_R0805"))
    )
    (comp (ref "R106")
      (value "R-EU_R0805")
      (footprint "eagle-import:R0805")
      (libsource (lib "eagle-import") (part "R-EU_R0805"))
    )
    (comp (ref "R107")
      (value "R-EU_R0805")
      (footprint "eagle-import:R0805")
      (libsource (lib "eagle-import") (part "R-EU_R0805"))
    )
    (comp (ref "R108")
      (value "R-EU_R0805")
      (footprint "eagle-import:R0805")
      (libsource (lib "eagle-import") (part "R-EU_R0805"))
    )
    (comp (ref "R109")
      (value "R-EU_R0805")
      (footprint "eagle-import:R0805")
      (libsource (lib "eagle-import") (part "R-EU_R0805"))
    )
    (comp (ref "R110")
      (value "R-EU_R0805")
      (footprint "eagle-import:R0805")
      (libsource (lib "eagle-import") (part "R-EU_R0805"))
    )
    (comp (ref "TTL-RS1")
      (value "TTL-RS485")
      (footprint "eagle-import:TTL-RS485")
      (libsource (lib "eagle-import") (part "TTL-RS485"))
    )
    (comp (ref "U$1")
      (value "FIDUCIAL")
      (footprint "eagle-import:FIDUCIAL_1MM")
      (libsource (lib "eagle-import") (part "FIDUCIAL"))
    )
    (comp (ref "U$2")
      (value "FIDUCIAL")
      (footprint "eagle-import:FIDUCIAL_1MM")
      (libsource (lib "eagle-import") (part "FIDUCIAL"))
    )
    (comp (ref "U$3")
      (value "FIDUCIAL")
      (footprint "eagle-import:FIDUCIAL_1MM")
      (libsource (lib "eagle-import") (part "FIDUCIAL"))
    )
    (comp (ref "U$4")
      (value "FIDUCIAL")
      (footprint "eagle-import:FIDUCIAL_1MM")
      (libsource (lib "eagle-import") (part "FIDUCIAL"))
    )
    (comp (ref "U$5")
      (value "FIDUCIAL")
      (footprint "eagle-import:FIDUCIAL_1MM")
      (libsource (lib "eagle-import") (part "FIDUCIAL"))
    )
    (comp (ref "U1")
      (value "PC817X2NIP0F")
      (footprint "eagle-import:SOT254P975X400-4N")
      (fields (field (name "MF") "Sharp Microelectronics"))
      (libsource (lib "eagle-import") (part "PC817X2NIP0F"))
    )
    (comp (ref "U2")
      (value "PC817X2NIP0F")
      (footprint "eagle-import:SOT254P975X400-4N")
      (fields (field (name "MF") "Sharp Microelectronics"))
      (libsource (lib "eagle-import") (part "PC817X2NIP0F"))
    )
    (comp (ref "U3")
      (value "PC817X2NIP0F")
      (footprint "eagle-import:SOT254P975X400-4N")
      (fields (field (name "MF") "Sharp Microelectronics"))
      (libsource (lib "eagle-import") (part "PC817X2NIP0F"))
    )
    (comp (ref "U4")
      (value "PC817X2NIP0F")
      (footprint "eagle-import:SOT254P975X400-4N")
      (fields (field (name "MF") "Sharp Microelectronics"))
      (libsource (lib "eagle-import") (part "PC817X2NIP0F"))
    )
    (comp (ref "U5")
      (value "PC817X2NIP0F")
      (footprint "eagle-import:SOT254P975X400-4N")
      (fields (field (name "MF") "Sharp Microelectronics"))
      (libsource (lib "eagle-import") (part "PC817X2NIP0F"))
    )
    (comp (ref "U6")
      (value "PC817X2NIP0F")
      (footprint "eagle-import:SOT254P975X400-4N")
      (fields (field (name "MF") "Sharp Microelectronics"))
      (libsource (lib "eagle-import") (part "PC817X2NIP0F"))
    )
    (comp (ref "U7")
      (value "PC817X2NIP0F")
      (footprint "eagle-import:SOT254P975X400-4N")
      (fields (field (name "MF") "Sharp Microelectronics"))
      (libsource (lib "eagle-import") (part "PC817X2NIP0F"))
    )
    (comp (ref "U8")
      (value "PC817X2NIP0F")
      (footprint "eagle-import:SOT254P975X400-4N")
      (fields (field (name "MF") "Sharp Microelectronics"))
      (libsource (lib "eagle-import") (part "PC817X2NIP0F"))
    )
    (comp (ref "USB2RS1")
      (value "USB2RS485")
      (footprint "eagle-import:USB2RS485")
      (libsource (lib "eagle-import") (part "USB2RS485"))
    )
    (comp (ref "Z1")
      (value "DIODE-SOD123")
      (footprint "eagle-import:SOD123")
      (libsource (lib "eagle-import") (part "DIODE-SOD123"))
    )
    (comp (ref "Z2")
      (value "DIODE-SOD123")
      (footprint "eagle-import:SOD123")
      (libsource (lib "eagle-import") (part "DIODE-SOD123"))
    )
    (comp (ref "Z3")
      (value "DIODE-SOD123")
      (footprint "eagle-import:SOD123")
      (libsource (lib "eagle-import") (part "DIODE-SOD123"))
    )
    (comp (ref "Z4")
      (value "DIODE-SOD123")
      (footprint "eagle-import:SOD123")
      (libsource (lib "eagle-import") (part "DIODE-SOD123"))
    )
    (comp (ref "Z5")
      (value "DIODE-SOD123")
      (footprint "eagle-import:SOD123")
      (libsource (lib "eagle-import") (part "DIODE-SOD123"))
    )
    (comp (ref "Z6")
      (value "DIODE-SOD123")
      (footprint "eagle-import:SOD123")
      (libsource (lib "eagle-import") (part "DIODE-SOD123"))
    )
    (comp (ref "Z7")
      (value "DIODE-SOD123")
      (footprint "eagle-import:SOD123")
      (libsource (lib "eagle-import") (part "DIODE-SOD123"))
    )
    (comp (ref "Z8")
      (value "DIODE-SOD123")
      (footprint "eagle-import:SOD123")
      (libsource (lib "eagle-import") (part "DIODE-SOD123"))
    )
    (comp (ref "Z9")
      (value "DIODE-SOD123")
      (footprint "eagle-import:SOD123")
      (libsource (lib "eagle-import") (part "DIODE-SOD123"))
    )
    (comp (ref "Z10")
      (value "DIODE-SOD123")
      (footprint "eagle-import:SOD123")
      (libsource (lib "eagle-import") (part "DIODE-SOD123"))
    )
    (comp (ref "Z11")
      (value "DIODE-SOD123")
      (footprint "eagle-import:SOD123")
      (libsource (lib "eagle-import") (part "DIODE-SOD123"))
    )
    (comp (ref "Z12")
      (value "DIODE-SOD123")
      (footprint "eagle-import:SOD123")
      (libsource (lib "eagle-import") (part "DIODE-SOD123"))
    )
    (comp (ref "Z13")
      (value "DIODE-SOD123")
      (footprint "eagle-import:SOD123")
      (libsource (lib "eagle-import") (part "DIODE-SOD123"))
    )
    (comp (ref "Z14")
      (value "DIODE-SOD123")
      (footprint "eagle-import:SOD123")
      (libsource (lib "eagle-import") (part "DIODE-SOD123"))
    )
    (comp (ref "Z15")
      (value "DIODE-SOD123")
      (footprint "eagle-import:SOD123")
      (libsource (lib "eagle-import") (part "DIODE-SOD123"))
    )
    (comp (ref "Z16")
      (value "DIODE-SOD123")
      (footprint "eagle-import:SOD123")
      (libsource (lib "eagle-import") (part "DIODE-SOD123"))
    )
    (comp (ref "Z17")
      (value "DIODE-SOD123")
      (footprint "eagle-import:SOD123")
      (libsource (lib "eagle-import") (part "DIODE-SOD123"))
    )
    (comp (ref "Z18")
      (value "DIODE-SOD123")
      (footprint "eagle-import:SOD123")
      (libsource (lib "eagle-import") (part "DIODE-SOD123"))
    )
    (comp (ref "Z19")
      (value "DIODE-SOD123")
      (footprint "eagle-import:SOD123")
      (libsource (lib "eagle-import") (part "DIODE-SOD123"))
    )
    (comp (ref "Z20")
      (value "DIODE-SOD123")
      (footprint "eagle-import:SOD123")
      (libsource (lib "eagle-import") (part "DIODE-SOD123"))
    )
    (comp (ref "Z21")
      (value "DIODE-SOD123")
      (footprint "eagle-import:SOD123")
      (libsource (lib "eagle-import") (part "DIODE-SOD123"))
    )
    (comp (ref "Z22")
      (value "DIODE-SOD123")
      (footprint "eagle-import:SOD123")
      (libsource (lib "eagle-import") (part "DIODE-SOD123"))
    )
    (comp (ref "Z23")
      (value "DIODE-SOD123")
      (footprint "eagle-import:SOD123")
      (libsource (lib "eagle-import") (part "DIODE-SOD123"))
    )
    (comp (ref "Z24")
      (value "DIODE-SOD123")
      (footprint "eagle-import:SOD123")
      (libsource (lib "eagle-import") (part "DIODE-SOD123"))
    )
    (comp (ref "Z25")
      (value "DIODE-SOD123")
      (footprint "eagle-import:SOD123")
      (libsource (lib "eagle-import") (part "DIODE-SOD123"))
    )
    (comp (ref "Z26")
      (value "DIODE-SOD123")
      (footprint "eagle-import:SOD123")
      (libsource (lib "eagle-import") (part "DIODE-SOD123"))
    )
    (comp (ref "Z27")
      (value "DIODE-SOD123")
      (footprint "eagle-import:SOD123")
      (libsource (lib "eagle-import") (part "DIODE-SOD123"))
    )
    (comp (ref "Z28")
      (value "DIODE-SOD123")
      (footprint "eagle-import:SOD123")
      (libsource (lib "eagle-import") (part "DIODE-SOD123"))
    )
    (comp (ref "Z29")
      (value "DIODE-SOD123")
      (footprint "eagle-import:SOD123")
      (libsource (lib "eagle-import") (part "DIODE-SOD123"))
    )
    (comp (ref "Z30")
      (value "DIODE-SOD123")
      (footprint "eagle-import:SOD123")
      (libsource (lib "eagle-import") (part "DIODE-SOD123"))
    )
    (comp (ref "Z31")
      (value "DIODE-SOD123")
      (footprint "eagle-import:SOD123")
      (libsource (lib "eagle-import") (part "DIODE-SOD123"))
    )
    (comp (ref "Z32")
      (value "DIODE-SOD123")
      (footprint "eagle-import:SOD123")
      (libsource (lib "eagle-import") (part "DIODE-SOD123"))
    )
  )
  (nets
    (net (code "1") (name "/COMM") (class "Default")
      (node (ref "HEADER-22P1") (pin "20") (pinfunction "20_20") (pintype "bidirectional"))
      (node (ref "OPTO1") (pin "2") (pinfunction "C_2") (pintype "passive"))
      (node (ref "OPTO10") (pin "2") (pinfunction "C_2") (pintype "passive"))
      (node (ref "OPTO11") (pin "2") (pinfunction "C_2") (pintype "passive"))
      (node (ref "OPTO12") (pin "2") (pinfunction "C_2") (pintype "passive"))
      (node (ref "OPTO13") (pin "2") (pinfunction "C_2") (pintype "passive"))
      (node (ref "OPTO14") (pin "2") (pinfunction "C_2") (pintype "passive"))
      (node (ref "OPTO15") (pin "2") (pinfunction "C_2") (pintype "passive"))
      (node (ref "OPTO16") (pin "2") (pinfunction "C_2") (pintype "passive"))
      (node (ref "OPTO17") (pin "2") (pinfunction "C_2") (pintype "passive"))
      (node (ref "OPTO18") (pin "2") (pinfunction "C_2") (pintype "passive"))
      (node (ref "OPTO19") (pin "2") (pinfunction "C_2") (pintype "passive"))
      (node (ref "OPTO2") (pin "2") (pinfunction "C_2") (pintype "passive"))
      (node (ref "OPTO20") (pin "2") (pinfunction "C_2") (pintype "passive"))
      (node (ref "OPTO21") (pin "2") (pinfunction "C_2") (pintype "passive"))
      (node (ref "OPTO22") (pin "2") (pinfunction "C_2") (pintype "passive"))
      (node (ref "OPTO23") (pin "2") (pinfunction "C_2") (pintype "passive"))
      (node (ref "OPTO24") (pin "2") (pinfunction "C_2") (pintype "passive"))
      (node (ref "OPTO25") (pin "2") (pinfunction "C_2") (pintype "passive"))
      (node (ref "OPTO26") (pin "2") (pinfunction "C_2") (pintype "passive"))
      (node (ref "OPTO27") (pin "2") (pinfunction "C_2") (pintype "passive"))
      (node (ref "OPTO28") (pin "2") (pinfunction "C_2") (pintype "passive"))
      (node (ref "OPTO29") (pin "2") (pinfunction "C_2") (pintype "passive"))
      (node (ref "OPTO3") (pin "2") (pinfunction "C_2") (pintype "passive"))
      (node (ref "OPTO30") (pin "2") (pinfunction "C_2") (pintype "passive"))
      (node (ref "OPTO31") (pin "2") (pinfunction "C_2") (pintype "passive"))
      (node (ref "OPTO32") (pin "2") (pinfunction "C_2") (pintype "passive"))
      (node (ref "OPTO4") (pin "2") (pinfunction "C_2") (pintype "passive"))
      (node (ref "OPTO5") (pin "2") (pinfunction "C_2") (pintype "passive"))
      (node (ref "OPTO6") (pin "2") (pinfunction "C_2") (pintype "passive"))
      (node (ref "OPTO7") (pin "2") (pinfunction "C_2") (pintype "passive"))
      (node (ref "OPTO8") (pin "2") (pinfunction "C_2") (pintype "passive"))
      (node (ref "OPTO9") (pin "2") (pinfunction "C_2") (pintype "passive"))
      (node (ref "Z1") (pin "A") (pinfunction "A_A") (pintype "passive"))
      (node (ref "Z10") (pin "A") (pinfunction "A_A") (pintype "passive"))
      (node (ref "Z11") (pin "A") (pinfunction "A_A") (pintype "passive"))
      (node (ref "Z12") (pin "A") (pinfunction "A_A") (pintype "passive"))
      (node (ref "Z13") (pin "A") (pinfunction "A_A") (pintype "passive"))
      (node (ref "Z14") (pin "A") (pinfunction "A_A") (pintype "passive"))
      (node (ref "Z15") (pin "A") (pinfunction "A_A") (pintype "passive"))
      (node (ref "Z16") (pin "A") (pinfunction "A_A") (pintype "passive"))
      (node (ref "Z17") (pin "A") (pinfunction "A_A") (pintype "passive"))
      (node (ref "Z18") (pin "A") (pinfunction "A_A") (pintype "passive"))
      (node (ref "Z19") (pin "A") (pinfunction "A_A") (pintype "passive"))
      (node (ref "Z2") (pin "A") (pinfunction "A_A") (pintype "passive"))
      (node (ref "Z20") (pin "A") (pinfunction "A_A") (pintype "passive"))
      (node (ref "Z21") (pin "A") (pinfunction "A_A") (pintype "passive"))
      (node (ref "Z22") (pin "A") (pinfunction "A_A") (pintype "passive"))
      (node (ref "Z23") (pin "A") (pinfunction "A_A") (pintype "passive"))
      (node (ref "Z24") (pin "A") (pinfunction "A_A") (pintype "passive"))
      (node (ref "Z25") (pin "A") (pinfunction "A_A") (pintype "passive"))
      (node (ref "Z26") (pin "A") (pinfunction "A_A") (pintype "passive"))
      (node (ref "Z27") (pin "A") (pinfunction "A_A") (pintype "passive"))
      (node (ref "Z28") (pin "A") (pinfunction "A_A") (pintype "passive"))
      (node (ref "Z29") (pin "A") (pinfunction "A_A") (pintype "passive"))
      (node (ref "Z3") (pin "A") (pinfunction "A_A") (pintype "passive"))
      (node (ref "Z30") (pin "A") (pinfunction "A_A") (pintype "passive"))
      (node (ref "Z31") (pin "A") (pinfunction "A_A") (pintype "passive"))
      (node (ref "Z32") (pin "A") (pinfunction "A_A") (pintype "passive"))
      (node (ref "Z4") (pin "A") (pinfunction "A_A") (pintype "passive"))
      (node (ref "Z5") (pin "A") (pinfunction "A_A") (pintype "passive"))
      (node (ref "Z6") (pin "A") (pinfunction "A_A") (pintype "passive"))
      (node (ref "Z7") (pin "A") (pinfunction "A_A") (pintype "passive"))
      (node (ref "Z8") (pin "A") (pinfunction "A_A") (pintype "passive"))
      (node (ref "Z9") (pin "A") (pinfunction "A_A") (pintype "passive"))
    )
    (net (code "2") (name "/NO_PDO1") (class "Default")
      (node (ref "HEADER-22P1") (pin "4") (pinfunction "4_4") (pintype "bidirectional"))
      (node (ref "K2") (pin "S1") (pinfunction "S_S1") (pintype "passive"))
    )
    (net (code "3") (name "/OUT1") (class "Default")
      (node (ref "IC4") (pin "21") (pinfunction "GPA0_21") (pintype "bidirectional"))
      (node (ref "OPTO1") (pin "4") (pinfunction "CT_4") (pintype "passive"))
      (node (ref "R49") (pin "1") (pinfunction "1_1") (pintype "passive"))
    )
    (net (code "4") (name "/OUT2") (class "Default")
      (node (ref "IC4") (pin "22") (pinfunction "GPA1_22") (pintype "bidirectional"))
      (node (ref "OPTO2") (pin "4") (pinfunction "CT_4") (pintype "passive"))
      (node (ref "R50") (pin "1") (pinfunction "1_1") (pintype "passive"))
    )
    (net (code "5") (name "/OUT3") (class "Default")
      (node (ref "IC4") (pin "23") (pinfunction "GPA2_23") (pintype "bidirectional"))
      (node (ref "OPTO3") (pin "4") (pinfunction "CT_4") (pintype "passive"))
      (node (ref "R51") (pin "1") (pinfunction "1_1") (pintype "passive"))
    )
    (net (code "6") (name "/OUT4") (class "Default")
      (node (ref "IC4") (pin "24") (pinfunction "GPA3_24") (pintype "bidirectional"))
      (node (ref "OPTO4") (pin "4") (pinfunction "CT_4") (pintype "passive"))
      (node (ref "R52") (pin "1") (pinfunction "1_1") (pintype "passive"))
    )
    (net (code "7") (name "/OUT5") (class "Default")
      (node (ref "IC4") (pin "25") (pinfunction "GPA4_25") (pintype "bidirectional"))
      (node (ref "OPTO5") (pin "4") (pinfunction "CT_4") (pintype "passive"))
      (node (ref "R53") (pin "1") (pinfunction "1_1") (pintype "passive"))
    )
    (net (code "8") (name "/OUT6") (class "Default")
      (node (ref "IC4") (pin "26") (pinfunction "GPA5_26") (pintype "bidirectional"))
      (node (ref "OPTO6") (pin "4") (pinfunction "CT_4") (pintype "passive"))
      (node (ref "R54") (pin "1") (pinfunction "1_1") (pintype "passive"))
    )
    (net (code "9") (name "/OUT7") (class "Default")
      (node (ref "IC4") (pin "27") (pinfunction "GPA6_27") (pintype "bidirectional"))
      (node (ref "OPTO7") (pin "4") (pinfunction "CT_4") (pintype "passive"))
      (node (ref "R55") (pin "1") (pinfunction "1_1") (pintype "passive"))
    )
    (net (code "10") (name "/OUT8") (class "Default")
      (node (ref "IC4") (pin "28") (pinfunction "GPA7_28") (pintype "bidirectional"))
      (node (ref "OPTO8") (pin "4") (pinfunction "CT_4") (pintype "passive"))
      (node (ref "R56") (pin "1") (pinfunction "1_1") (pintype "passive"))
    )
    (net (code "11") (name "/OUT9") (class "Default")
      (node (ref "IC4") (pin "1") (pinfunction "GPB0_1") (pintype "bidirectional"))
      (node (ref "OPTO9") (pin "4") (pinfunction "CT_4") (pintype "passive"))
      (node (ref "R57") (pin "1") (pinfunction "1_1") (pintype "passive"))
    )
    (net (code "12") (name "/OUT10") (class "Default")
      (node (ref "IC4") (pin "2") (pinfunction "GPB1_2") (pintype "bidirectional"))
      (node (ref "OPTO10") (pin "4") (pinfunction "CT_4") (pintype "passive"))
      (node (ref "R58") (pin "1") (pinfunction "1_1") (pintype "passive"))
    )
    (net (code "13") (name "/OUT11") (class "Default")
      (node (ref "IC4") (pin "3") (pinfunction "GPB2_3") (pintype "bidirectional"))
      (node (ref "OPTO11") (pin "4") (pinfunction "CT_4") (pintype "passive"))
      (node (ref "R59") (pin "1") (pinfunction "1_1") (pintype "passive"))
    )
    (net (code "14") (name "/OUT12") (class "Default")
      (node (ref "IC4") (pin "4") (pinfunction "GPB3_4") (pintype "bidirectional"))
      (node (ref "OPTO12") (pin "4") (pinfunction "CT_4") (pintype "passive"))
      (node (ref "R60") (pin "1") (pinfunction "1_1") (pintype "passive"))
    )
    (net (code "15") (name "/OUT13") (class "Default")
      (node (ref "IC4") (pin "5") (pinfunction "GPB4_5") (pintype "bidirectional"))
      (node (ref "OPTO13") (pin "4") (pinfunction "CT_4") (pintype "passive"))
      (node (ref "R61") (pin "1") (pinfunction "1_1") (pintype "passive"))
    )
    (net (code "16") (name "/OUT14") (class "Default")
      (node (ref "IC4") (pin "6") (pinfunction "GPB5_6") (pintype "bidirectional"))
      (node (ref "OPTO14") (pin "4") (pinfunction "CT_4") (pintype "passive"))
      (node (ref "R62") (pin "1") (pinfunction "1_1") (pintype "passive"))
    )
    (net (code "17") (name "/OUT15") (class "Default")
      (node (ref "IC4") (pin "7") (pinfunction "GPB6_7") (pintype "bidirectional"))
      (node (ref "OPTO15") (pin "4") (pinfunction "CT_4") (pintype "passive"))
      (node (ref "R63") (pin "1") (pinfunction "1_1") (pintype "passive"))
    )
    (net (code "18") (name "/OUT16") (class "Default")
      (node (ref "IC4") (pin "8") (pinfunction "GPB7_8") (pintype "bidirectional"))
      (node (ref "OPTO16") (pin "4") (pinfunction "CT_4") (pintype "passive"))
      (node (ref "R64") (pin "1") (pinfunction "1_1") (pintype "passive"))
    )
    (net (code "19") (name "/OUT17") (class "Default")
      (node (ref "IC1") (pin "21") (pinfunction "GPA0_21") (pintype "bidirectional"))
      (node (ref "OPTO17") (pin "4") (pinfunction "CT_4") (pintype "passive"))
      (node (ref "R65") (pin "1") (pinfunction "1_1") (pintype "passive"))
    )
    (net (code "20") (name "/OUT18") (class "Default")
      (node (ref "IC1") (pin "22") (pinfunction "GPA1_22") (pintype "bidirectional"))
      (node (ref "OPTO18") (pin "4") (pinfunction "CT_4") (pintype "passive"))
      (node (ref "R66") (pin "1") (pinfunction "1_1") (pintype "passive"))
    )
    (net (code "21") (name "/OUT19") (class "Default")
      (node (ref "IC1") (pin "23") (pinfunction "GPA2_23") (pintype "bidirectional"))
      (node (ref "OPTO19") (pin "4") (pinfunction "CT_4") (pintype "passive"))
      (node (ref "R67") (pin "1") (pinfunction "1_1") (pintype "passive"))
    )
    (net (code "22") (name "/OUT20") (class "Default")
      (node (ref "IC1") (pin "24") (pinfunction "GPA3_24") (pintype "bidirectional"))
      (node (ref "OPTO20") (pin "4") (pinfunction "CT_4") (pintype "passive"))
      (node (ref "R68") (pin "1") (pinfunction "1_1") (pintype "passive"))
    )
    (net (code "23") (name "/OUT21") (class "Default")
      (node (ref "IC1") (pin "25") (pinfunction "GPA4_25") (pintype "bidirectional"))
      (node (ref "OPTO21") (pin "4") (pinfunction "CT_4") (pintype "passive"))
      (node (ref "R69") (pin "1") (pinfunction "1_1") (pintype "passive"))
    )
    (net (code "24") (name "/OUT22") (class "Default")
      (node (ref "IC1") (pin "26") (pinfunction "GPA5_26") (pintype "bidirectional"))
      (node (ref "OPTO22") (pin "4") (pinfunction "CT_4") (pintype "passive"))
      (node (ref "R70") (pin "1") (pinfunction "1_1") (pintype "passive"))
    )
    (net (code "25") (name "/OUT23") (class "Default")
      (node (ref "IC1") (pin "27") (pinfunction "GPA6_27") (pintype "bidirectional"))
      (node (ref "OPTO23") (pin "4") (pinfunction "CT_4") (pintype "passive"))
      (node (ref "R71") (pin "1") (pinfunction "1_1") (pintype "passive"))
    )
    (net (code "26") (name "/OUT24") (class "Default")
      (node (ref "IC1") (pin "28") (pinfunction "GPA7_28") (pintype "bidirectional"))
      (node (ref "OPTO24") (pin "4") (pinfunction "CT_4") (pintype "passive"))
      (node (ref "R72") (pin "1") (pinfunction "1_1") (pintype "passive"))
    )
    (net (code "27") (name "/OUT25") (class "Default")
      (node (ref "IC1") (pin "1") (pinfunction "GPB0_1") (pintype "bidirectional"))
      (node (ref "OPTO25") (pin "4") (pinfunction "CT_4") (pintype "passive"))
      (node (ref "R73") (pin "1") (pinfunction "1_1") (pintype "passive"))
    )
    (net (code "28") (name "/OUT26") (class "Default")
      (node (ref "IC1") (pin "2") (pinfunction "GPB1_2") (pintype "bidirectional"))
      (node (ref "OPTO26") (pin "4") (pinfunction "CT_4") (pintype "passive"))
      (node (ref "R74") (pin "1") (pinfunction "1_1") (pintype "passive"))
    )
    (net (code "29") (name "/OUT27") (class "Default")
      (node (ref "IC1") (pin "3") (pinfunction "GPB2_3") (pintype "bidirectional"))
      (node (ref "OPTO27") (pin "4") (pinfunction "CT_4") (pintype "passive"))
      (node (ref "R75") (pin "1") (pinfunction "1_1") (pintype "passive"))
    )
    (net (code "30") (name "/OUT28") (class "Default")
      (node (ref "IC1") (pin "4") (pinfunction "GPB3_4") (pintype "bidirectional"))
      (node (ref "OPTO28") (pin "4") (pinfunction "CT_4") (pintype "passive"))
      (node (ref "R76") (pin "1") (pinfunction "1_1") (pintype "passive"))
    )
    (net (code "31") (name "/OUT29") (class "Default")
      (node (ref "IC1") (pin "5") (pinfunction "GPB4_5") (pintype "bidirectional"))
      (node (ref "OPTO29") (pin "4") (pinfunction "CT_4") (pintype "passive"))
      (node (ref "R77") (pin "1") (pinfunction "1_1") (pintype "passive"))
    )
    (net (code "32") (name "/OUT30") (class "Default")
      (node (ref "IC1") (pin "6") (pinfunction "GPB5_6") (pintype "bidirectional"))
      (node (ref "OPTO30") (pin "4") (pinfunction "CT_4") (pintype "passive"))
      (node (ref "R78") (pin "1") (pinfunction "1_1") (pintype "passive"))
    )
    (net (code "33") (name "/OUT31") (class "Default")
      (node (ref "IC1") (pin "7") (pinfunction "GPB6_7") (pintype "bidirectional"))
      (node (ref "OPTO31") (pin "4") (pinfunction "CT_4") (pintype "passive"))
      (node (ref "R79") (pin "1") (pinfunction "1_1") (pintype "passive"))
    )
    (net (code "34") (name "/OUT32") (class "Default")
      (node (ref "IC1") (pin "8") (pinfunction "GPB7_8") (pintype "bidirectional"))
      (node (ref "OPTO32") (pin "4") (pinfunction "CT_4") (pintype "passive"))
      (node (ref "R80") (pin "1") (pinfunction "1_1") (pintype "passive"))
    )
    (net (code "35") (name "/P1") (class "Default")
      (node (ref "HEADER-29P1") (pin "1") (pinfunction "1_1") (pintype "bidirectional"))
      (node (ref "R1") (pin "1") (pinfunction "1_1") (pintype "passive"))
    )
    (net (code "36") (name "/P2") (class "Default")
      (node (ref "HEADER-29P1") (pin "2") (pinfunction "2_2") (pintype "bidirectional"))
      (node (ref "R2") (pin "1") (pinfunction "1_1") (pintype "passive"))
    )
    (net (code "37") (name "/P3") (class "Default")
      (node (ref "HEADER-29P1") (pin "3") (pinfunction "3_3") (pintype "bidirectional"))
      (node (ref "R3") (pin "1") (pinfunction "1_1") (pintype "passive"))
    )
    (net (code "38") (name "/P4") (class "Default")
      (node (ref "HEADER-29P1") (pin "4") (pinfunction "4_4") (pintype "bidirectional"))
      (node (ref "R4") (pin "1") (pinfunction "1_1") (pintype "passive"))
    )
    (net (code "39") (name "/P5") (class "Default")
      (node (ref "HEADER-29P1") (pin "5") (pinfunction "5_5") (pintype "bidirectional"))
      (node (ref "R5") (pin "1") (pinfunction "1_1") (pintype "passive"))
    )
    (net (code "40") (name "/P6") (class "Default")
      (node (ref "HEADER-29P1") (pin "6") (pinfunction "6_6") (pintype "bidirectional"))
      (node (ref "R6") (pin "1") (pinfunction "1_1") (pintype "passive"))
    )
    (net (code "41") (name "/P7") (class "Default")
      (node (ref "HEADER-29P1") (pin "7") (pinfunction "7_7") (pintype "bidirectional"))
      (node (ref "R7") (pin "1") (pinfunction "1_1") (pintype "passive"))
    )
    (net (code "42") (name "/P8") (class "Default")
      (node (ref "HEADER-29P1") (pin "8") (pinfunction "8_8") (pintype "bidirectional"))
      (node (ref "R8") (pin "1") (pinfunction "1_1") (pintype "passive"))
    )
    (net (code "43") (name "/P9") (class "Default")
      (node (ref "HEADER-29P1") (pin "9") (pinfunction "9_9") (pintype "bidirectional"))
      (node (ref "R9") (pin "1") (pinfunction "1_1") (pintype "passive"))
    )
    (net (code "44") (name "/P10") (class "Default")
      (node (ref "HEADER-29P1") (pin "10") (pinfunction "10_10") (pintype "bidirectional"))
      (node (ref "R10") (pin "1") (pinfunction "1_1") (pintype "passive"))
    )
    (net (code "45") (name "/P11") (class "Default")
      (node (ref "HEADER-29P1") (pin "11") (pinfunction "11_11") (pintype "bidirectional"))
      (node (ref "R11") (pin "1") (pinfunction "1_1") (pintype "passive"))
    )
    (net (code "46") (name "/P12") (class "Default")
      (node (ref "HEADER-29P1") (pin "12") (pinfunction "12_12") (pintype "bidirectional"))
      (node (ref "R12") (pin "1") (pinfunction "1_1") (pintype "passive"))
    )
    (net (code "47") (name "/P13") (class "Default")
      (node (ref "HEADER-29P1") (pin "13") (pinfunction "13_13") (pintype "bidirectional"))
      (node (ref "R13") (pin "1") (pinfunction "1_1") (pintype "passive"))
    )
    (net (code "48") (name "/P14") (class "Default")
      (node (ref "HEADER-29P1") (pin "14") (pinfunction "14_14") (pintype "bidirectional"))
      (node (ref "R14") (pin "1") (pinfunction "1_1") (pintype "passive"))
    )
    (net (code "49") (name "/P15") (class "Default")
      (node (ref "HEADER-29P1") (pin "15") (pinfunction "15_15") (pintype "bidirectional"))
      (node (ref "R15") (pin "1") (pinfunction "1_1") (pintype "passive"))
    )
    (net (code "50") (name "/P16") (class "Default")
      (node (ref "HEADER-29P1") (pin "16") (pinfunction "16_16") (pintype "bidirectional"))
      (node (ref "R16") (pin "1") (pinfunction "1_1") (pintype "passive"))
    )
    (net (code "51") (name "/P17") (class "Default")
      (node (ref "HEADER-29P1") (pin "17") (pinfunction "17_17") (pintype "bidirectional"))
      (node (ref "R17") (pin "1") (pinfunction "1_1") (pintype "passive"))
    )
    (net (code "52") (name "/P18") (class "Default")
      (node (ref "HEADER-29P1") (pin "18") (pinfunction "18_18") (pintype "bidirectional"))
      (node (ref "R18") (pin "1") (pinfunction "1_1") (pintype "passive"))
    )
    (net (code "53") (name "/P19") (class "Default")
      (node (ref "HEADER-29P1") (pin "19") (pinfunction "19_19") (pintype "bidirectional"))
      (node (ref "R19") (pin "1") (pinfunction "1_1") (pintype "passive"))
    )
    (net (code "54") (name "/P20") (class "Default")
      (node (ref "HEADER-29P1") (pin "20") (pinfunction "20_20") (pintype "bidirectional"))
      (node (ref "R20") (pin "1") (pinfunction "1_1") (pintype "passive"))
    )
    (net (code "55") (name "/P21") (class "Default")
      (node (ref "HEADER-29P1") (pin "21") (pinfunction "21_21") (pintype "bidirectional"))
      (node (ref "R21") (pin "1") (pinfunction "1_1") (pintype "passive"))
    )
    (net (code "56") (name "/P22") (class "Default")
      (node (ref "HEADER-29P1") (pin "22") (pinfunction "22_22") (pintype "bidirectional"))
      (node (ref "R22") (pin "1") (pinfunction "1_1") (pintype "passive"))
    )
    (net (code "57") (name "/P23") (class "Default")
      (node (ref "HEADER-29P1") (pin "23") (pinfunction "23_23") (pintype "bidirectional"))
      (node (ref "R23") (pin "1") (pinfunction "1_1") (pintype "passive"))
    )
    (net (code "58") (name "/P24") (class "Default")
      (node (ref "HEADER-29P1") (pin "24") (pinfunction "24_24") (pintype "bidirectional"))
      (node (ref "R24") (pin "1") (pinfunction "1_1") (pintype "passive"))
    )
    (net (code "59") (name "/P25") (class "Default")
      (node (ref "HEADER-29P1") (pin "25") (pinfunction "25_25") (pintype "bidirectional"))
      (node (ref "R25") (pin "1") (pinfunction "1_1") (pintype "passive"))
    )
    (net (code "60") (name "/P26") (class "Default")
      (node (ref "HEADER-29P1") (pin "26") (pinfunction "26_26") (pintype "bidirectional"))
      (node (ref "R26") (pin "1") (pinfunction "1_1") (pintype "passive"))
    )
    (net (code "61") (name "/P27") (class "Default")
      (node (ref "HEADER-29P1") (pin "27") (pinfunction "27_27") (pintype "bidirectional"))
      (node (ref "R27") (pin "1") (pinfunction "1_1") (pintype "passive"))
    )
    (net (code "62") (name "/P28") (class "Default")
      (node (ref "HEADER-29P1") (pin "28") (pinfunction "28_28") (pintype "bidirectional"))
      (node (ref "R28") (pin "1") (pinfunction "1_1") (pintype "passive"))
    )
    (net (code "63") (name "/P29") (class "Default")
      (node (ref "HEADER-29P1") (pin "29") (pinfunction "29_29") (pintype "bidirectional"))
      (node (ref "R29") (pin "1") (pinfunction "1_1") (pintype "passive"))
    )
    (net (code "64") (name "/P30") (class "Default")
      (node (ref "HEADER-22P1") (pin "1") (pinfunction "1_1") (pintype "bidirectional"))
      (node (ref "R30") (pin "1") (pinfunction "1_1") (pintype "passive"))
    )
    (net (code "65") (name "/P31") (class "Default")
      (node (ref "HEADER-22P1") (pin "2") (pinfunction "2_2") (pintype "bidirectional"))
      (node (ref "R31") (pin "1") (pinfunction "1_1") (pintype "passive"))
    )
    (net (code "66") (name "/P32") (class "Default")
      (node (ref "HEADER-22P1") (pin "3") (pinfunction "3_3") (pintype "bidirectional"))
      (node (ref "R32") (pin "1") (pinfunction "1_1") (pintype "passive"))
    )
    (net (code "67") (name "24V+") (class "Default")
      (node (ref "HEADER-22P1") (pin "22") (pinfunction "22_22") (pintype "bidirectional"))
      (node (ref "JP1") (pin "P$1") (pinfunction "1_P$1") (pintype "passive"))
    )
    (net (code "68") (name "A+") (class "Default")
      (node (ref "JP2") (pin "7") (pinfunction "7_7") (pintype "passive"))
      (node (ref "TTL-RS1") (pin "A") (pinfunction "A_A") (pintype "bidirectional"))
    )
    (net (code "69") (name "B-") (class "Default")
      (node (ref "JP2") (pin "5") (pinfunction "5_5") (pintype "passive"))
      (node (ref "TTL-RS1") (pin "B") (pinfunction "B_B") (pintype "bidirectional"))
    )
    (net (code "70") (name "COM_PDO1") (class "Default")
      (node (ref "HEADER-22P1") (pin "5") (pinfunction "5_5") (pintype "bidirectional"))
      (node (ref "K2") (pin "P1") (pinfunction "P_P1") (pintype "passive"))
    )
    (net (code "71") (name "COM_PDO2") (class "Default")
      (node (ref "HEADER-22P1") (pin "7") (pinfunction "7_7") (pintype "bidirectional"))
      (node (ref "K3") (pin "P1") (pinfunction "P_P1") (pintype "passive"))
    )
    (net (code "72") (name "COM_PDO3") (class "Default")
      (node (ref "HEADER-22P1") (pin "9") (pinfunction "9_9") (pintype "bidirectional"))
      (node (ref "K4") (pin "P1") (pinfunction "P_P1") (pintype "passive"))
    )
    (net (code "73") (name "COM_PDO4") (class "Default")
      (node (ref "HEADER-22P1") (pin "11") (pinfunction "11_11") (pintype "bidirectional"))
      (node (ref "K5") (pin "P1") (pinfunction "P_P1") (pintype "passive"))
    )
    (net (code "74") (name "COM_PDO5") (class "Default")
      (node (ref "HEADER-22P1") (pin "13") (pinfunction "13_13") (pintype "bidirectional"))
      (node (ref "K6") (pin "P1") (pinfunction "P_P1") (pintype "passive"))
    )
    (net (code "75") (name "COM_PDO6") (class "Default")
      (node (ref "HEADER-22P1") (pin "15") (pinfunction "15_15") (pintype "bidirectional"))
      (node (ref "K7") (pin "P1") (pinfunction "P_P1") (pintype "passive"))
    )
    (net (code "76") (name "COM_PDO7") (class "Default")
      (node (ref "HEADER-22P1") (pin "17") (pinfunction "17_17") (pintype "bidirectional"))
      (node (ref "K8") (pin "P1") (pinfunction "P_P1") (pintype "passive"))
    )
    (net (code "77") (name "COM_PDO8") (class "Default")
      (node (ref "HEADER-22P1") (pin "19") (pinfunction "19_19") (pintype "bidirectional"))
      (node (ref "K9") (pin "P1") (pinfunction "P_P1") (pintype "passive"))
    )
    (net (code "78") (name "DO1") (class "Default")
      (node (ref "JP5") (pin "1") (pinfunction "1_1") (pintype "passive"))
      (node (ref "R34") (pin "2") (pinfunction "2_2") (pintype "passive"))
    )
    (net (code "79") (name "DO2") (class "Default")
      (node (ref "JP5") (pin "2") (pinfunction "2_2") (pintype "passive"))
      (node (ref "R36") (pin "2") (pinfunction "2_2") (pintype "passive"))
    )
    (net (code "80") (name "DO3") (class "Default")
      (node (ref "JP5") (pin "3") (pinfunction "3_3") (pintype "passive"))
      (node (ref "R38") (pin "2") (pinfunction "2_2") (pintype "passive"))
    )
    (net (code "81") (name "DO4") (class "Default")
      (node (ref "JP5") (pin "4") (pinfunction "4_4") (pintype "passive"))
      (node (ref "R40") (pin "2") (pinfunction "2_2") (pintype "passive"))
    )
    (net (code "82") (name "DO5") (class "Default")
      (node (ref "JP5") (pin "5") (pinfunction "5_5") (pintype "passive"))
      (node (ref "R42") (pin "2") (pinfunction "2_2") (pintype "passive"))
    )
    (net (code "83") (name "DO6") (class "Default")
      (node (ref "JP5") (pin "6") (pinfunction "6_6") (pintype "passive"))
      (node (ref "R44") (pin "2") (pinfunction "2_2") (pintype "passive"))
    )
    (net (code "84") (name "DO7") (class "Default")
      (node (ref "JP5") (pin "7") (pinfunction "7_7") (pintype "passive"))
      (node (ref "R46") (pin "2") (pinfunction "2_2") (pintype "passive"))
    )
    (net (code "85") (name "DO8") (class "Default")
      (node (ref "JP5") (pin "8") (pinfunction "8_8") (pintype "passive"))
      (node (ref "R48") (pin "2") (pinfunction "2_2") (pintype "passive"))
    )
    (net (code "86") (name "GND") (class "Default")
      (node (ref "IC1") (pin "10") (pinfunction "VSS_10") (pintype "power_in"))
      (node (ref "IC4") (pin "10") (pinfunction "VSS_10") (pintype "power_in"))
      (node (ref "JP2") (pin "2") (pinfunction "2_2") (pintype "passive"))
      (node (ref "JP4") (pin "2") (pinfunction "2_2") (pintype "passive"))
      (node (ref "JP4") (pin "4") (pinfunction "4_4") (pintype "passive"))
      (node (ref "OPTO1") (pin "3") (pinfunction "ET_3") (pintype "passive"))
      (node (ref "OPTO10") (pin "3") (pinfunction "ET_3") (pintype "passive"))
      (node (ref "OPTO11") (pin "3") (pinfunction "ET_3") (pintype "passive"))
      (node (ref "OPTO12") (pin "3") (pinfunction "ET_3") (pintype "passive"))
      (node (ref "OPTO13") (pin "3") (pinfunction "ET_3") (pintype "passive"))
      (node (ref "OPTO14") (pin "3") (pinfunction "ET_3") (pintype "passive"))
      (node (ref "OPTO15") (pin "3") (pinfunction "ET_3") (pintype "passive"))
      (node (ref "OPTO16") (pin "3") (pinfunction "ET_3") (pintype "passive"))
      (node (ref "OPTO17") (pin "3") (pinfunction "ET_3") (pintype "passive"))
      (node (ref "OPTO18") (pin "3") (pinfunction "ET_3") (pintype "passive"))
      (node (ref "OPTO19") (pin "3") (pinfunction "ET_3") (pintype "passive"))
      (node (ref "OPTO2") (pin "3") (pinfunction "ET_3") (pintype "passive"))
      (node (ref "OPTO20") (pin "3") (pinfunction "ET_3") (pintype "passive"))
      (node (ref "OPTO21") (pin "3") (pinfunction "ET_3") (pintype "passive"))
      (node (ref "OPTO22") (pin "3") (pinfunction "ET_3") (pintype "passive"))
      (node (ref "OPTO23") (pin "3") (pinfunction "ET_3") (pintype "passive"))
      (node (ref "OPTO24") (pin "3") (pinfunction "ET_3") (pintype "passive"))
      (node (ref "OPTO25") (pin "3") (pinfunction "ET_3") (pintype "passive"))
      (node (ref "OPTO26") (pin "3") (pinfunction "ET_3") (pintype "passive"))
      (node (ref "OPTO27") (pin "3") (pinfunction "ET_3") (pintype "passive"))
      (node (ref "OPTO28") (pin "3") (pinfunction "ET_3") (pintype "passive"))
      (node (ref "OPTO29") (pin "3") (pinfunction "ET_3") (pintype "passive"))
      (node (ref "OPTO3") (pin "3") (pinfunction "ET_3") (pintype "passive"))
      (node (ref "OPTO30") (pin "3") (pinfunction "ET_3") (pintype "passive"))
      (node (ref "OPTO31") (pin "3") (pinfunction "ET_3") (pintype "passive"))
      (node (ref "OPTO32") (pin "3") (pinfunction "ET_3") (pintype "passive"))
      (node (ref "OPTO4") (pin "3") (pinfunction "ET_3") (pintype "passive"))
      (node (ref "OPTO5") (pin "3") (pinfunction "ET_3") (pintype "passive"))
      (node (ref "OPTO6") (pin "3") (pinfunction "ET_3") (pintype "passive"))
      (node (ref "OPTO7") (pin "3") (pinfunction "ET_3") (pintype "passive"))
      (node (ref "OPTO8") (pin "3") (pinfunction "ET_3") (pintype "passive"))
      (node (ref "OPTO9") (pin "3") (pinfunction "ET_3") (pintype "passive"))
      (node (ref "Q2") (pin "2") (pinfunction "E_2") (pintype "passive"))
      (node (ref "Q3") (pin "2") (pinfunction "E_2") (pintype "passive"))
      (node (ref "Q4") (pin "2") (pinfunction "E_2") (pintype "passive"))
      (node (ref "Q5") (pin "2") (pinfunction "E_2") (pintype "passive"))
      (node (ref "Q6") (pin "2") (pinfunction "E_2") (pintype "passive"))
      (node (ref "Q7") (pin "2") (pinfunction "E_2") (pintype "passive"))
      (node (ref "Q8") (pin "2") (pinfunction "E_2") (pintype "passive"))
      (node (ref "Q9") (pin "2") (pinfunction "E_2") (pintype "passive"))
      (node (ref "R104") (pin "1") (pinfunction "1_1") (pintype "passive"))
      (node (ref "R105") (pin "1") (pinfunction "1_1") (pintype "passive"))
      (node (ref "R106") (pin "1") (pinfunction "1_1") (pintype "passive"))
      (node (ref "R109") (pin "1") (pinfunction "1_1") (pintype "passive"))
      (node (ref "R110") (pin "1") (pinfunction "1_1") (pintype "passive"))
      (node (ref "TTL-RS1") (pin "GND") (pinfunction "GND_GND") (pintype "bidirectional"))
      (node (ref "U1") (pin "2") (pinfunction "C_2") (pintype "passive"))
      (node (ref "U2") (pin "2") (pinfunction "C_2") (pintype "passive"))
      (node (ref "U3") (pin "2") (pinfunction "C_2") (pintype "passive"))
      (node (ref "U4") (pin "2") (pinfunction "C_2") (pintype "passive"))
      (node (ref "U5") (pin "2") (pinfunction "C_2") (pintype "passive"))
      (node (ref "U6") (pin "2") (pinfunction "C_2") (pintype "passive"))
      (node (ref "U7") (pin "2") (pinfunction "C_2") (pintype "passive"))
      (node (ref "U8") (pin "2") (pinfunction "C_2") (pintype "passive"))
      (node (ref "USB2RS1") (pin "4") (pinfunction "4_4") (pintype "bidirectional"))
    )
    (net (code "87") (name "NO_PDO2") (class "Default")
      (node (ref "HEADER-22P1") (pin "6") (pinfunction "6_6") (pintype "bidirectional"))
      (node (ref "K3") (pin "S1") (pinfunction "S_S1") (pintype "passive"))
    )
    (net (code "88") (name "NO_PDO3") (class "Default")
      (node (ref "HEADER-22P1") (pin "8") (pinfunction "8_8") (pintype "bidirectional"))
      (node (ref "K4") (pin "S1") (pinfunction "S_S1") (pintype "passive"))
    )
    (net (code "89") (name "NO_PDO4") (class "Default")
      (node (ref "HEADER-22P1") (pin "10") (pinfunction "10_10") (pintype "bidirectional"))
      (node (ref "K5") (pin "S1") (pinfunction "S_S1") (pintype "passive"))
    )
    (net (code "90") (name "NO_PDO5") (class "Default")
      (node (ref "HEADER-22P1") (pin "12") (pinfunction "12_12") (pintype "bidirectional"))
      (node (ref "K6") (pin "S1") (pinfunction "S_S1") (pintype "passive"))
    )
    (net (code "91") (name "NO_PDO6") (class "Default")
      (node (ref "HEADER-22P1") (pin "14") (pinfunction "14_14") (pintype "bidirectional"))
      (node (ref "K7") (pin "S1") (pinfunction "S_S1") (pintype "passive"))
    )
    (net (code "92") (name "NO_PDO7") (class "Default")
      (node (ref "HEADER-22P1") (pin "16") (pinfunction "16_16") (pintype "bidirectional"))
      (node (ref "K8") (pin "S1") (pinfunction "S_S1") (pintype "passive"))
    )
    (net (code "93") (name "NO_PDO8") (class "Default")
      (node (ref "HEADER-22P1") (pin "18") (pinfunction "18_18") (pintype "bidirectional"))
      (node (ref "K9") (pin "S1") (pinfunction "S_S1") (pintype "passive"))
    )
    (net (code "94") (name "Net-(D2-K)") (class "Default")
      (node (ref "D2") (pin "C") (pinfunction "K_C") (pintype "passive"))
      (node (ref "LED1") (pin "+") (pinfunction "+_+") (pintype "passive"))
    )
    (net (code "95") (name "Net-(D2-PadA)") (class "Default")
      (node (ref "D2") (pin "A") (pinfunction "A_A") (pintype "passive"))
      (node (ref "R1") (pin "2") (pinfunction "2_2") (pintype "passive"))
    )
    (net (code "96") (name "Net-(D3-K)") (class "Default")
      (node (ref "D3") (pin "C") (pinfunction "K_C") (pintype "passive"))
      (node (ref "LED2") (pin "+") (pinfunction "+_+") (pintype "passive"))
    )
    (net (code "97") (name "Net-(D3-PadA)") (class "Default")
      (node (ref "D3") (pin "A") (pinfunction "A_A") (pintype "passive"))
      (node (ref "R2") (pin "2") (pinfunction "2_2") (pintype "passive"))
    )
    (net (code "98") (name "Net-(D4-K)") (class "Default")
      (node (ref "D4") (pin "C") (pinfunction "K_C") (pintype "passive"))
      (node (ref "LED3") (pin "+") (pinfunction "+_+") (pintype "passive"))
    )
    (net (code "99") (name "Net-(D4-PadA)") (class "Default")
      (node (ref "D4") (pin "A") (pinfunction "A_A") (pintype "passive"))
      (node (ref "R3") (pin "2") (pinfunction "2_2") (pintype "passive"))
    )
    (net (code "100") (name "Net-(D5-K)") (class "Default")
      (node (ref "D5") (pin "C") (pinfunction "K_C") (pintype "passive"))
      (node (ref "LED4") (pin "+") (pinfunction "+_+") (pintype "passive"))
    )
    (net (code "101") (name "Net-(D5-PadA)") (class "Default")
      (node (ref "D5") (pin "A") (pinfunction "A_A") (pintype "passive"))
      (node (ref "R4") (pin "2") (pinfunction "2_2") (pintype "passive"))
    )
    (net (code "102") (name "Net-(D6-K)") (class "Default")
      (node (ref "D6") (pin "C") (pinfunction "K_C") (pintype "passive"))
      (node (ref "LED5") (pin "+") (pinfunction "+_+") (pintype "passive"))
    )
    (net (code "103") (name "Net-(D6-PadA)") (class "Default")
      (node (ref "D6") (pin "A") (pinfunction "A_A") (pintype "passive"))
      (node (ref "R5") (pin "2") (pinfunction "2_2") (pintype "passive"))
    )
    (net (code "104") (name "Net-(D7-K)") (class "Default")
      (node (ref "D7") (pin "C") (pinfunction "K_C") (pintype "passive"))
      (node (ref "LED6") (pin "+") (pinfunction "+_+") (pintype "passive"))
    )
    (net (code "105") (name "Net-(D7-PadA)") (class "Default")
      (node (ref "D7") (pin "A") (pinfunction "A_A") (pintype "passive"))
      (node (ref "R6") (pin "2") (pinfunction "2_2") (pintype "passive"))
    )
    (net (code "106") (name "Net-(D8-K)") (class "Default")
      (node (ref "D8") (pin "C") (pinfunction "K_C") (pintype "passive"))
      (node (ref "LED7") (pin "+") (pinfunction "+_+") (pintype "passive"))
    )
    (net (code "107") (name "Net-(D8-PadA)") (class "Default")
      (node (ref "D8") (pin "A") (pinfunction "A_A") (pintype "passive"))
      (node (ref "R7") (pin "2") (pinfunction "2_2") (pintype "passive"))
    )
    (net (code "108") (name "Net-(D9-K)") (class "Default")
      (node (ref "D9") (pin "C") (pinfunction "K_C") (pintype "passive"))
      (node (ref "LED8") (pin "+") (pinfunction "+_+") (pintype "passive"))
    )
    (net (code "109") (name "Net-(D9-PadA)") (class "Default")
      (node (ref "D9") (pin "A") (pinfunction "A_A") (pintype "passive"))
      (node (ref "R8") (pin "2") (pinfunction "2_2") (pintype "passive"))
    )
    (net (code "110") (name "Net-(D10-K)") (class "Default")
      (node (ref "D10") (pin "C") (pinfunction "K_C") (pintype "passive"))
      (node (ref "LED9") (pin "+") (pinfunction "+_+") (pintype "passive"))
    )
    (net (code "111") (name "Net-(D10-PadA)") (class "Default")
      (node (ref "D10") (pin "A") (pinfunction "A_A") (pintype "passive"))
      (node (ref "R9") (pin "2") (pinfunction "2_2") (pintype "passive"))
    )
    (net (code "112") (name "Net-(D11-K)") (class "Default")
      (node (ref "D11") (pin "C") (pinfunction "K_C") (pintype "passive"))
      (node (ref "LED10") (pin "+") (pinfunction "+_+") (pintype "passive"))
    )
    (net (code "113") (name "Net-(D11-PadA)") (class "Default")
      (node (ref "D11") (pin "A") (pinfunction "A_A") (pintype "passive"))
      (node (ref "R10") (pin "2") (pinfunction "2_2") (pintype "passive"))
    )
    (net (code "114") (name "Net-(D12-K)") (class "Default")
      (node (ref "D12") (pin "C") (pinfunction "K_C") (pintype "passive"))
      (node (ref "LED11") (pin "+") (pinfunction "+_+") (pintype "passive"))
    )
    (net (code "115") (name "Net-(D12-PadA)") (class "Default")
      (node (ref "D12") (pin "A") (pinfunction "A_A") (pintype "passive"))
      (node (ref "R11") (pin "2") (pinfunction "2_2") (pintype "passive"))
    )
    (net (code "116") (name "Net-(D13-K)") (class "Default")
      (node (ref "D13") (pin "C") (pinfunction "K_C") (pintype "passive"))
      (node (ref "LED12") (pin "+") (pinfunction "+_+") (pintype "passive"))
    )
    (net (code "117") (name "Net-(D13-PadA)") (class "Default")
      (node (ref "D13") (pin "A") (pinfunction "A_A") (pintype "passive"))
      (node (ref "R12") (pin "2") (pinfunction "2_2") (pintype "passive"))
    )
    (net (code "118") (name "Net-(D14-K)") (class "Default")
      (node (ref "D14") (pin "C") (pinfunction "K_C") (pintype "passive"))
      (node (ref "LED13") (pin "+") (pinfunction "+_+") (pintype "passive"))
    )
    (net (code "119") (name "Net-(D14-PadA)") (class "Default")
      (node (ref "D14") (pin "A") (pinfunction "A_A") (pintype "passive"))
      (node (ref "R13") (pin "2") (pinfunction "2_2") (pintype "passive"))
    )
    (net (code "120") (name "Net-(D15-K)") (class "Default")
      (node (ref "D15") (pin "C") (pinfunction "K_C") (pintype "passive"))
      (node (ref "LED14") (pin "+") (pinfunction "+_+") (pintype "passive"))
    )
    (net (code "121") (name "Net-(D15-PadA)") (class "Default")
      (node (ref "D15") (pin "A") (pinfunction "A_A") (pintype "passive"))
      (node (ref "R14") (pin "2") (pinfunction "2_2") (pintype "passive"))
    )
    (net (code "122") (name "Net-(D16-K)") (class "Default")
      (node (ref "D16") (pin "C") (pinfunction "K_C") (pintype "passive"))
      (node (ref "LED15") (pin "+") (pinfunction "+_+") (pintype "passive"))
    )
    (net (code "123") (name "Net-(D16-PadA)") (class "Default")
      (node (ref "D16") (pin "A") (pinfunction "A_A") (pintype "passive"))
      (node (ref "R15") (pin "2") (pinfunction "2_2") (pintype "passive"))
    )
    (net (code "124") (name "Net-(D17-K)") (class "Default")
      (node (ref "D17") (pin "C") (pinfunction "K_C") (pintype "passive"))
      (node (ref "LED16") (pin "+") (pinfunction "+_+") (pintype "passive"))
    )
    (net (code "125") (name "Net-(D17-PadA)") (class "Default")
      (node (ref "D17") (pin "A") (pinfunction "A_A") (pintype "passive"))
      (node (ref "R16") (pin "2") (pinfunction "2_2") (pintype "passive"))
    )
    (net (code "126") (name "Net-(D18-K)") (class "Default")
      (node (ref "D18") (pin "C") (pinfunction "K_C") (pintype "passive"))
      (node (ref "LED17") (pin "+") (pinfunction "+_+") (pintype "passive"))
    )
    (net (code "127") (name "Net-(D18-PadA)") (class "Default")
      (node (ref "D18") (pin "A") (pinfunction "A_A") (pintype "passive"))
      (node (ref "R17") (pin "2") (pinfunction "2_2") (pintype "passive"))
    )
    (net (code "128") (name "Net-(D19-K)") (class "Default")
      (node (ref "D19") (pin "C") (pinfunction "K_C") (pintype "passive"))
      (node (ref "LED18") (pin "+") (pinfunction "+_+") (pintype "passive"))
    )
    (net (code "129") (name "Net-(D19-PadA)") (class "Default")
      (node (ref "D19") (pin "A") (pinfunction "A_A") (pintype "passive"))
      (node (ref "R18") (pin "2") (pinfunction "2_2") (pintype "passive"))
    )
    (net (code "130") (name "Net-(D20-K)") (class "Default")
      (node (ref "D20") (pin "C") (pinfunction "K_C") (pintype "passive"))
      (node (ref "LED19") (pin "+") (pinfunction "+_+") (pintype "passive"))
    )
    (net (code "131") (name "Net-(D20-PadA)") (class "Default")
      (node (ref "D20") (pin "A") (pinfunction "A_A") (pintype "passive"))
      (node (ref "R19") (pin "2") (pinfunction "2_2") (pintype "passive"))
    )
    (net (code "132") (name "Net-(D21-K)") (class "Default")
      (node (ref "D21") (pin "C") (pinfunction "K_C") (pintype "passive"))
      (node (ref "LED20") (pin "+") (pinfunction "+_+") (pintype "passive"))
    )
    (net (code "133") (name "Net-(D21-PadA)") (class "Default")
      (node (ref "D21") (pin "A") (pinfunction "A_A") (pintype "passive"))
      (node (ref "R20") (pin "2") (pinfunction "2_2") (pintype "passive"))
    )
    (net (code "134") (name "Net-(D22-K)") (class "Default")
      (node (ref "D22") (pin "C") (pinfunction "K_C") (pintype "passive"))
      (node (ref "LED21") (pin "+") (pinfunction "+_+") (pintype "passive"))
    )
    (net (code "135") (name "Net-(D22-PadA)") (class "Default")
      (node (ref "D22") (pin "A") (pinfunction "A_A") (pintype "passive"))
      (node (ref "R21") (pin "2") (pinfunction "2_2") (pintype "passive"))
    )
    (net (code "136") (name "Net-(D23-K)") (class "Default")
      (node (ref "D23") (pin "C") (pinfunction "K_C") (pintype "passive"))
      (node (ref "LED22") (pin "+") (pinfunction "+_+") (pintype "passive"))
    )
    (net (code "137") (name "Net-(D23-PadA)") (class "Default")
      (node (ref "D23") (pin "A") (pinfunction "A_A") (pintype "passive"))
      (node (ref "R22") (pin "2") (pinfunction "2_2") (pintype "passive"))
    )
    (net (code "138") (name "Net-(D24-K)") (class "Default")
      (node (ref "D24") (pin "C") (pinfunction "K_C") (pintype "passive"))
      (node (ref "LED23") (pin "+") (pinfunction "+_+") (pintype "passive"))
    )
    (net (code "139") (name "Net-(D24-PadA)") (class "Default")
      (node (ref "D24") (pin "A") (pinfunction "A_A") (pintype "passive"))
      (node (ref "R23") (pin "2") (pinfunction "2_2") (pintype "passive"))
    )
    (net (code "140") (name "Net-(D25-K)") (class "Default")
      (node (ref "D25") (pin "C") (pinfunction "K_C") (pintype "passive"))
      (node (ref "LED24") (pin "+") (pinfunction "+_+") (pintype "passive"))
    )
    (net (code "141") (name "Net-(D25-PadA)") (class "Default")
      (node (ref "D25") (pin "A") (pinfunction "A_A") (pintype "passive"))
      (node (ref "R24") (pin "2") (pinfunction "2_2") (pintype "passive"))
    )
    (net (code "142") (name "Net-(D26-K)") (class "Default")
      (node (ref "D26") (pin "C") (pinfunction "K_C") (pintype "passive"))
      (node (ref "LED25") (pin "+") (pinfunction "+_+") (pintype "passive"))
    )
    (net (code "143") (name "Net-(D26-PadA)") (class "Default")
      (node (ref "D26") (pin "A") (pinfunction "A_A") (pintype "passive"))
      (node (ref "R25") (pin "2") (pinfunction "2_2") (pintype "passive"))
    )
    (net (code "144") (name "Net-(D27-K)") (class "Default")
      (node (ref "D27") (pin "C") (pinfunction "K_C") (pintype "passive"))
      (node (ref "LED26") (pin "+") (pinfunction "+_+") (pintype "passive"))
    )
    (net (code "145") (name "Net-(D27-PadA)") (class "Default")
      (node (ref "D27") (pin "A") (pinfunction "A_A") (pintype "passive"))
      (node (ref "R26") (pin "2") (pinfunction "2_2") (pintype "passive"))
    )
    (net (code "146") (name "Net-(D28-K)") (class "Default")
      (node (ref "D28") (pin "C") (pinfunction "K_C") (pintype "passive"))
      (node (ref "LED27") (pin "+") (pinfunction "+_+") (pintype "passive"))
    )
    (net (code "147") (name "Net-(D28-PadA)") (class "Default")
      (node (ref "D28") (pin "A") (pinfunction "A_A") (pintype "passive"))
      (node (ref "R27") (pin "2") (pinfunction "2_2") (pintype "passive"))
    )
    (net (code "148") (name "Net-(D29-K)") (class "Default")
      (node (ref "D29") (pin "C") (pinfunction "K_C") (pintype "passive"))
      (node (ref "LED28") (pin "+") (pinfunction "+_+") (pintype "passive"))
    )
    (net (code "149") (name "Net-(D29-PadA)") (class "Default")
      (node (ref "D29") (pin "A") (pinfunction "A_A") (pintype "passive"))
      (node (ref "R28") (pin "2") (pinfunction "2_2") (pintype "passive"))
    )
    (net (code "150") (name "Net-(D30-K)") (class "Default")
      (node (ref "D30") (pin "C") (pinfunction "K_C") (pintype "passive"))
      (node (ref "LED29") (pin "+") (pinfunction "+_+") (pintype "passive"))
    )
    (net (code "151") (name "Net-(D30-PadA)") (class "Default")
      (node (ref "D30") (pin "A") (pinfunction "A_A") (pintype "passive"))
      (node (ref "R29") (pin "2") (pinfunction "2_2") (pintype "passive"))
    )
    (net (code "152") (name "Net-(D31-K)") (class "Default")
      (node (ref "D31") (pin "C") (pinfunction "K_C") (pintype "passive"))
      (node (ref "LED30") (pin "+") (pinfunction "+_+") (pintype "passive"))
    )
    (net (code "153") (name "Net-(D31-PadA)") (class "Default")
      (node (ref "D31") (pin "A") (pinfunction "A_A") (pintype "passive"))
      (node (ref "R30") (pin "2") (pinfunction "2_2") (pintype "passive"))
    )
    (net (code "154") (name "Net-(D32-K)") (class "Default")
      (node (ref "D32") (pin "C") (pinfunction "K_C") (pintype "passive"))
      (node (ref "LED31") (pin "+") (pinfunction "+_+") (pintype "passive"))
    )
    (net (code "155") (name "Net-(D32-PadA)") (class "Default")
      (node (ref "D32") (pin "A") (pinfunction "A_A") (pintype "passive"))
      (node (ref "R31") (pin "2") (pinfunction "2_2") (pintype "passive"))
    )
    (net (code "156") (name "Net-(D33-K)") (class "Default")
      (node (ref "D33") (pin "C") (pinfunction "K_C") (pintype "passive"))
      (node (ref "LED32") (pin "+") (pinfunction "+_+") (pintype "passive"))
    )
    (net (code "157") (name "Net-(D33-PadA)") (class "Default")
      (node (ref "D33") (pin "A") (pinfunction "A_A") (pintype "passive"))
      (node (ref "R32") (pin "2") (pinfunction "2_2") (pintype "passive"))
    )
    (net (code "158") (name "Net-(IC1-A0)") (class "Default")
      (node (ref "IC1") (pin "15") (pinfunction "A0_15") (pintype "input"))
      (node (ref "R108") (pin "2") (pinfunction "2_2") (pintype "passive"))
    )
    (net (code "159") (name "Net-(IC1-A1)") (class "Default")
      (node (ref "IC1") (pin "16") (pinfunction "A1_16") (pintype "input"))
      (node (ref "R109") (pin "2") (pinfunction "2_2") (pintype "passive"))
    )
    (net (code "160") (name "Net-(IC1-A2)") (class "Default")
      (node (ref "IC1") (pin "17") (pinfunction "A2_17") (pintype "input"))
      (node (ref "R110") (pin "2") (pinfunction "2_2") (pintype "passive"))
    )
    (net (code "161") (name "Net-(IC1-~{RESET})") (class "Default")
      (node (ref "IC1") (pin "18") (pinfunction "~{RESET}_18") (pintype "input"))
      (node (ref "R107") (pin "1") (pinfunction "1_1") (pintype "passive"))
    )
    (net (code "162") (name "Net-(IC4-A0)") (class "Default")
      (node (ref "IC4") (pin "15") (pinfunction "A0_15") (pintype "input"))
      (node (ref "R106") (pin "2") (pinfunction "2_2") (pintype "passive"))
    )
    (net (code "163") (name "Net-(IC4-A1)") (class "Default")
      (node (ref "IC4") (pin "16") (pinfunction "A1_16") (pintype "input"))
      (node (ref "R105") (pin "2") (pinfunction "2_2") (pintype "passive"))
    )
    (net (code "164") (name "Net-(IC4-A2)") (class "Default")
      (node (ref "IC4") (pin "17") (pinfunction "A2_17") (pintype "input"))
      (node (ref "R104") (pin "2") (pinfunction "2_2") (pintype "passive"))
    )
    (net (code "165") (name "Net-(IC4-~{RESET})") (class "Default")
      (node (ref "IC4") (pin "18") (pinfunction "~{RESET}_18") (pintype "input"))
      (node (ref "R103") (pin "2") (pinfunction "2_2") (pintype "passive"))
    )
    (net (code "166") (name "Net-(JP3-1)") (class "Default")
      (node (ref "HEADER-22P1") (pin "21") (pinfunction "21_21") (pintype "bidirectional"))
      (node (ref "JP3") (pin "P$1") (pinfunction "1_P$1") (pintype "passive"))
    )
    (net (code "167") (name "Net-(K2A-2)") (class "Default")
      (node (ref "D34") (pin "A") (pinfunction "A_A") (pintype "passive"))
      (node (ref "K2") (pin "16") (pinfunction "2_16") (pintype "passive"))
      (node (ref "Q2") (pin "3") (pinfunction "C_3") (pintype "passive"))
    )
    (net (code "168") (name "Net-(K3A-2)") (class "Default")
      (node (ref "D36") (pin "A") (pinfunction "A_A") (pintype "passive"))
      (node (ref "K3") (pin "16") (pinfunction "2_16") (pintype "passive"))
      (node (ref "Q3") (pin "3") (pinfunction "C_3") (pintype "passive"))
    )
    (net (code "169") (name "Net-(K4A-2)") (class "Default")
      (node (ref "D38") (pin "A") (pinfunction "A_A") (pintype "passive"))
      (node (ref "K4") (pin "16") (pinfunction "2_16") (pintype "passive"))
      (node (ref "Q4") (pin "3") (pinfunction "C_3") (pintype "passive"))
    )
    (net (code "170") (name "Net-(K5A-2)") (class "Default")
      (node (ref "D40") (pin "A") (pinfunction "A_A") (pintype "passive"))
      (node (ref "K5") (pin "16") (pinfunction "2_16") (pintype "passive"))
      (node (ref "Q5") (pin "3") (pinfunction "C_3") (pintype "passive"))
    )
    (net (code "171") (name "Net-(K6A-2)") (class "Default")
      (node (ref "D42") (pin "A") (pinfunction "A_A") (pintype "passive"))
      (node (ref "K6") (pin "16") (pinfunction "2_16") (pintype "passive"))
      (node (ref "Q6") (pin "3") (pinfunction "C_3") (pintype "passive"))
    )
    (net (code "172") (name "Net-(K7A-2)") (class "Default")
      (node (ref "D44") (pin "A") (pinfunction "A_A") (pintype "passive"))
      (node (ref "K7") (pin "16") (pinfunction "2_16") (pintype "passive"))
      (node (ref "Q7") (pin "3") (pinfunction "C_3") (pintype "passive"))
    )
    (net (code "173") (name "Net-(K8A-2)") (class "Default")
      (node (ref "D46") (pin "A") (pinfunction "A_A") (pintype "passive"))
      (node (ref "K8") (pin "16") (pinfunction "2_16") (pintype "passive"))
      (node (ref "Q8") (pin "3") (pinfunction "C_3") (pintype "passive"))
    )
    (net (code "174") (name "Net-(K9A-2)") (class "Default")
      (node (ref "D48") (pin "A") (pinfunction "A_A") (pintype "passive"))
      (node (ref "K9") (pin "16") (pinfunction "2_16") (pintype "passive"))
      (node (ref "Q9") (pin "3") (pinfunction "C_3") (pintype "passive"))
    )
    (net (code "175") (name "Net-(LED33-Pad+)") (class "Default")
      (node (ref "LED33") (pin "+") (pinfunction "+_+") (pintype "passive"))
      (node (ref "R46") (pin "1") (pinfunction "1_1") (pintype "passive"))
    )
    (net (code "176") (name "Net-(LED34-Pad+)") (class "Default")
      (node (ref "LED34") (pin "+") (pinfunction "+_+") (pintype "passive"))
      (node (ref "R42") (pin "1") (pinfunction "1_1") (pintype "passive"))
    )
    (net (code "177") (name "Net-(LED35-Pad+)") (class "Default")
      (node (ref "LED35") (pin "+") (pinfunction "+_+") (pintype "passive"))
      (node (ref "R44") (pin "1") (pinfunction "1_1") (pintype "passive"))
    )
    (net (code "178") (name "Net-(LED36-Pad+)") (class "Default")
      (node (ref "LED36") (pin "+") (pinfunction "+_+") (pintype "passive"))
      (node (ref "R48") (pin "1") (pinfunction "1_1") (pintype "passive"))
    )
    (net (code "179") (name "Net-(LED37-Pad+)") (class "Default")
      (node (ref "LED37") (pin "+") (pinfunction "+_+") (pintype "passive"))
      (node (ref "R38") (pin "1") (pinfunction "1_1") (pintype "passive"))
    )
    (net (code "180") (name "Net-(LED38-Pad+)") (class "Default")
      (node (ref "LED38") (pin "+") (pinfunction "+_+") (pintype "passive"))
      (node (ref "R40") (pin "1") (pinfunction "1_1") (pintype "passive"))
    )
    (net (code "181") (name "Net-(LED39-Pad+)") (class "Default")
      (node (ref "LED39") (pin "+") (pinfunction "+_+") (pintype "passive"))
      (node (ref "R36") (pin "1") (pinfunction "1_1") (pintype "passive"))
    )
    (net (code "182") (name "Net-(LED40-Pad+)") (class "Default")
      (node (ref "LED40") (pin "+") (pinfunction "+_+") (pintype "passive"))
      (node (ref "R34") (pin "1") (pinfunction "1_1") (pintype "passive"))
    )
    (net (code "183") (name "Net-(OPTO1-A)") (class "Default")
      (node (ref "LED1") (pin "-") (pinfunction "-_-") (pintype "passive"))
      (node (ref "OPTO1") (pin "1") (pinfunction "A_1") (pintype "passive"))
      (node (ref "Z1") (pin "C") (pinfunction "C_C") (pintype "passive"))
    )
    (net (code "184") (name "Net-(OPTO2-A)") (class "Default")
      (node (ref "LED2") (pin "-") (pinfunction "-_-") (pintype "passive"))
      (node (ref "OPTO2") (pin "1") (pinfunction "A_1") (pintype "passive"))
      (node (ref "Z2") (pin "C") (pinfunction "C_C") (pintype "passive"))
    )
    (net (code "185") (name "Net-(OPTO3-A)") (class "Default")
      (node (ref "LED3") (pin "-") (pinfunction "-_-") (pintype "passive"))
      (node (ref "OPTO3") (pin "1") (pinfunction "A_1") (pintype "passive"))
      (node (ref "Z3") (pin "C") (pinfunction "C_C") (pintype "passive"))
    )
    (net (code "186") (name "Net-(OPTO4-A)") (class "Default")
      (node (ref "LED4") (pin "-") (pinfunction "-_-") (pintype "passive"))
      (node (ref "OPTO4") (pin "1") (pinfunction "A_1") (pintype "passive"))
      (node (ref "Z4") (pin "C") (pinfunction "C_C") (pintype "passive"))
    )
    (net (code "187") (name "Net-(OPTO5-A)") (class "Default")
      (node (ref "LED5") (pin "-") (pinfunction "-_-") (pintype "passive"))
      (node (ref "OPTO5") (pin "1") (pinfunction "A_1") (pintype "passive"))
      (node (ref "Z5") (pin "C") (pinfunction "C_C") (pintype "passive"))
    )
    (net (code "188") (name "Net-(OPTO6-A)") (class "Default")
      (node (ref "LED6") (pin "-") (pinfunction "-_-") (pintype "passive"))
      (node (ref "OPTO6") (pin "1") (pinfunction "A_1") (pintype "passive"))
      (node (ref "Z6") (pin "C") (pinfunction "C_C") (pintype "passive"))
    )
    (net (code "189") (name "Net-(OPTO7-A)") (class "Default")
      (node (ref "LED7") (pin "-") (pinfunction "-_-") (pintype "passive"))
      (node (ref "OPTO7") (pin "1") (pinfunction "A_1") (pintype "passive"))
      (node (ref "Z7") (pin "C") (pinfunction "C_C") (pintype "passive"))
    )
    (net (code "190") (name "Net-(OPTO8-A)") (class "Default")
      (node (ref "LED8") (pin "-") (pinfunction "-_-") (pintype "passive"))
      (node (ref "OPTO8") (pin "1") (pinfunction "A_1") (pintype "passive"))
      (node (ref "Z8") (pin "C") (pinfunction "C_C") (pintype "passive"))
    )
    (net (code "191") (name "Net-(OPTO9-A)") (class "Default")
      (node (ref "LED9") (pin "-") (pinfunction "-_-") (pintype "passive"))
      (node (ref "OPTO9") (pin "1") (pinfunction "A_1") (pintype "passive"))
      (node (ref "Z9") (pin "C") (pinfunction "C_C") (pintype "passive"))
    )
    (net (code "192") (name "Net-(OPTO10-A)") (class "Default")
      (node (ref "LED10") (pin "-") (pinfunction "-_-") (pintype "passive"))
      (node (ref "OPTO10") (pin "1") (pinfunction "A_1") (pintype "passive"))
      (node (ref "Z10") (pin "C") (pinfunction "C_C") (pintype "passive"))
    )
    (net (code "193") (name "Net-(OPTO11-A)") (class "Default")
      (node (ref "LED11") (pin "-") (pinfunction "-_-") (pintype "passive"))
      (node (ref "OPTO11") (pin "1") (pinfunction "A_1") (pintype "passive"))
      (node (ref "Z11") (pin "C") (pinfunction "C_C") (pintype "passive"))
    )
    (net (code "194") (name "Net-(OPTO12-A)") (class "Default")
      (node (ref "LED12") (pin "-") (pinfunction "-_-") (pintype "passive"))
      (node (ref "OPTO12") (pin "1") (pinfunction "A_1") (pintype "passive"))
      (node (ref "Z12") (pin "C") (pinfunction "C_C") (pintype "passive"))
    )
    (net (code "195") (name "Net-(OPTO13-A)") (class "Default")
      (node (ref "LED13") (pin "-") (pinfunction "-_-") (pintype "passive"))
      (node (ref "OPTO13") (pin "1") (pinfunction "A_1") (pintype "passive"))
      (node (ref "Z13") (pin "C") (pinfunction "C_C") (pintype "passive"))
    )
    (net (code "196") (name "Net-(OPTO14-A)") (class "Default")
      (node (ref "LED14") (pin "-") (pinfunction "-_-") (pintype "passive"))
      (node (ref "OPTO14") (pin "1") (pinfunction "A_1") (pintype "passive"))
      (node (ref "Z14") (pin "C") (pinfunction "C_C") (pintype "passive"))
    )
    (net (code "197") (name "Net-(OPTO15-A)") (class "Default")
      (node (ref "LED15") (pin "-") (pinfunction "-_-") (pintype "passive"))
      (node (ref "OPTO15") (pin "1") (pinfunction "A_1") (pintype "passive"))
      (node (ref "Z15") (pin "C") (pinfunction "C_C") (pintype "passive"))
    )
    (net (code "198") (name "Net-(OPTO16-A)") (class "Default")
      (node (ref "LED16") (pin "-") (pinfunction "-_-") (pintype "passive"))
      (node (ref "OPTO16") (pin "1") (pinfunction "A_1") (pintype "passive"))
      (node (ref "Z16") (pin "C") (pinfunction "C_C") (pintype "passive"))
    )
    (net (code "199") (name "Net-(OPTO17-A)") (class "Default")
      (node (ref "LED17") (pin "-") (pinfunction "-_-") (pintype "passive"))
      (node (ref "OPTO17") (pin "1") (pinfunction "A_1") (pintype "passive"))
      (node (ref "Z17") (pin "C") (pinfunction "C_C") (pintype "passive"))
    )
    (net (code "200") (name "Net-(OPTO18-A)") (class "Default")
      (node (ref "LED18") (pin "-") (pinfunction "-_-") (pintype "passive"))
      (node (ref "OPTO18") (pin "1") (pinfunction "A_1") (pintype "passive"))
      (node (ref "Z18") (pin "C") (pinfunction "C_C") (pintype "passive"))
    )
    (net (code "201") (name "Net-(OPTO19-A)") (class "Default")
      (node (ref "LED19") (pin "-") (pinfunction "-_-") (pintype "passive"))
      (node (ref "OPTO19") (pin "1") (pinfunction "A_1") (pintype "passive"))
      (node (ref "Z19") (pin "C") (pinfunction "C_C") (pintype "passive"))
    )
    (net (code "202") (name "Net-(OPTO20-A)") (class "Default")
      (node (ref "LED20") (pin "-") (pinfunction "-_-") (pintype "passive"))
      (node (ref "OPTO20") (pin "1") (pinfunction "A_1") (pintype "passive"))
      (node (ref "Z20") (pin "C") (pinfunction "C_C") (pintype "passive"))
    )
    (net (code "203") (name "Net-(OPTO21-A)") (class "Default")
      (node (ref "LED21") (pin "-") (pinfunction "-_-") (pintype "passive"))
      (node (ref "OPTO21") (pin "1") (pinfunction "A_1") (pintype "passive"))
      (node (ref "Z21") (pin "C") (pinfunction "C_C") (pintype "passive"))
    )
    (net (code "204") (name "Net-(OPTO22-A)") (class "Default")
      (node (ref "LED22") (pin "-") (pinfunction "-_-") (pintype "passive"))
      (node (ref "OPTO22") (pin "1") (pinfunction "A_1") (pintype "passive"))
      (node (ref "Z22") (pin "C") (pinfunction "C_C") (pintype "passive"))
    )
    (net (code "205") (name "Net-(OPTO23-A)") (class "Default")
      (node (ref "LED23") (pin "-") (pinfunction "-_-") (pintype "passive"))
      (node (ref "OPTO23") (pin "1") (pinfunction "A_1") (pintype "passive"))
      (node (ref "Z23") (pin "C") (pinfunction "C_C") (pintype "passive"))
    )
    (net (code "206") (name "Net-(OPTO24-A)") (class "Default")
      (node (ref "LED24") (pin "-") (pinfunction "-_-") (pintype "passive"))
      (node (ref "OPTO24") (pin "1") (pinfunction "A_1") (pintype "passive"))
      (node (ref "Z24") (pin "C") (pinfunction "C_C") (pintype "passive"))
    )
    (net (code "207") (name "Net-(OPTO25-A)") (class "Default")
      (node (ref "LED25") (pin "-") (pinfunction "-_-") (pintype "passive"))
      (node (ref "OPTO25") (pin "1") (pinfunction "A_1") (pintype "passive"))
      (node (ref "Z25") (pin "C") (pinfunction "C_C") (pintype "passive"))
    )
    (net (code "208") (name "Net-(OPTO26-A)") (class "Default")
      (node (ref "LED26") (pin "-") (pinfunction "-_-") (pintype "passive"))
      (node (ref "OPTO26") (pin "1") (pinfunction "A_1") (pintype "passive"))
      (node (ref "Z26") (pin "C") (pinfunction "C_C") (pintype "passive"))
    )
    (net (code "209") (name "Net-(OPTO27-A)") (class "Default")
      (node (ref "LED27") (pin "-") (pinfunction "-_-") (pintype "passive"))
      (node (ref "OPTO27") (pin "1") (pinfunction "A_1") (pintype "passive"))
      (node (ref "Z27") (pin "C") (pinfunction "C_C") (pintype "passive"))
    )
    (net (code "210") (name "Net-(OPTO28-A)") (class "Default")
      (node (ref "LED28") (pin "-") (pinfunction "-_-") (pintype "passive"))
      (node (ref "OPTO28") (pin "1") (pinfunction "A_1") (pintype "passive"))
      (node (ref "Z28") (pin "C") (pinfunction "C_C") (pintype "passive"))
    )
    (net (code "211") (name "Net-(OPTO29-A)") (class "Default")
      (node (ref "LED29") (pin "-") (pinfunction "-_-") (pintype "passive"))
      (node (ref "OPTO29") (pin "1") (pinfunction "A_1") (pintype "passive"))
      (node (ref "Z29") (pin "C") (pinfunction "C_C") (pintype "passive"))
    )
    (net (code "212") (name "Net-(OPTO30-A)") (class "Default")
      (node (ref "LED30") (pin "-") (pinfunction "-_-") (pintype "passive"))
      (node (ref "OPTO30") (pin "1") (pinfunction "A_1") (pintype "passive"))
      (node (ref "Z30") (pin "C") (pinfunction "C_C") (pintype "passive"))
    )
    (net (code "213") (name "Net-(OPTO31-A)") (class "Default")
      (node (ref "LED31") (pin "-") (pinfunction "-_-") (pintype "passive"))
      (node (ref "OPTO31") (pin "1") (pinfunction "A_1") (pintype "passive"))
      (node (ref "Z31") (pin "C") (pinfunction "C_C") (pintype "passive"))
    )
    (net (code "214") (name "Net-(OPTO32-A)") (class "Default")
      (node (ref "LED32") (pin "-") (pinfunction "-_-") (pintype "passive"))
      (node (ref "OPTO32") (pin "1") (pinfunction "A_1") (pintype "passive"))
      (node (ref "Z32") (pin "C") (pinfunction "C_C") (pintype "passive"))
    )
    (net (code "215") (name "Net-(Q2-B)") (class "Default")
      (node (ref "Q2") (pin "1") (pinfunction "B_1") (pintype "passive"))
      (node (ref "U1") (pin "3") (pinfunction "ET_3") (pintype "passive"))
    )
    (net (code "216") (name "Net-(Q3-B)") (class "Default")
      (node (ref "Q3") (pin "1") (pinfunction "B_1") (pintype "passive"))
      (node (ref "U2") (pin "3") (pinfunction "ET_3") (pintype "passive"))
    )
    (net (code "217") (name "Net-(Q4-B)") (class "Default")
      (node (ref "Q4") (pin "1") (pinfunction "B_1") (pintype "passive"))
      (node (ref "U3") (pin "3") (pinfunction "ET_3") (pintype "passive"))
    )
    (net (code "218") (name "Net-(Q5-B)") (class "Default")
      (node (ref "Q5") (pin "1") (pinfunction "B_1") (pintype "passive"))
      (node (ref "U4") (pin "3") (pinfunction "ET_3") (pintype "passive"))
    )
    (net (code "219") (name "Net-(Q6-B)") (class "Default")
      (node (ref "Q6") (pin "1") (pinfunction "B_1") (pintype "passive"))
      (node (ref "U5") (pin "3") (pinfunction "ET_3") (pintype "passive"))
    )
    (net (code "220") (name "Net-(Q7-B)") (class "Default")
      (node (ref "Q7") (pin "1") (pinfunction "B_1") (pintype "passive"))
      (node (ref "U6") (pin "3") (pinfunction "ET_3") (pintype "passive"))
    )
    (net (code "221") (name "Net-(Q8-B)") (class "Default")
      (node (ref "Q8") (pin "1") (pinfunction "B_1") (pintype "passive"))
      (node (ref "U7") (pin "3") (pinfunction "ET_3") (pintype "passive"))
    )
    (net (code "222") (name "Net-(Q9-B)") (class "Default")
      (node (ref "Q9") (pin "1") (pinfunction "B_1") (pintype "passive"))
      (node (ref "U8") (pin "3") (pinfunction "ET_3") (pintype "passive"))
    )
    (net (code "223") (name "Net-(U1-A)") (class "Default")
      (node (ref "LED40") (pin "-") (pinfunction "-_-") (pintype "passive"))
      (node (ref "U1") (pin "1") (pinfunction "A_1") (pintype "passive"))
    )
    (net (code "224") (name "Net-(U1-CT)") (class "Default")
      (node (ref "R33") (pin "1") (pinfunction "1_1") (pintype "passive"))
      (node (ref "U1") (pin "4") (pinfunction "CT_4") (pintype "passive"))
    )
    (net (code "225") (name "Net-(U2-A)") (class "Default")
      (node (ref "LED39") (pin "-") (pinfunction "-_-") (pintype "passive"))
      (node (ref "U2") (pin "1") (pinfunction "A_1") (pintype "passive"))
    )
    (net (code "226") (name "Net-(U2-CT)") (class "Default")
      (node (ref "R35") (pin "1") (pinfunction "1_1") (pintype "passive"))
      (node (ref "U2") (pin "4") (pinfunction "CT_4") (pintype "passive"))
    )
    (net (code "227") (name "Net-(U3-A)") (class "Default")
      (node (ref "LED37") (pin "-") (pinfunction "-_-") (pintype "passive"))
      (node (ref "U3") (pin "1") (pinfunction "A_1") (pintype "passive"))
    )
    (net (code "228") (name "Net-(U3-CT)") (class "Default")
      (node (ref "R37") (pin "1") (pinfunction "1_1") (pintype "passive"))
      (node (ref "U3") (pin "4") (pinfunction "CT_4") (pintype "passive"))
    )
    (net (code "229") (name "Net-(U4-A)") (class "Default")
      (node (ref "LED38") (pin "-") (pinfunction "-_-") (pintype "passive"))
      (node (ref "U4") (pin "1") (pinfunction "A_1") (pintype "passive"))
    )
    (net (code "230") (name "Net-(U4-CT)") (class "Default")
      (node (ref "R39") (pin "1") (pinfunction "1_1") (pintype "passive"))
      (node (ref "U4") (pin "4") (pinfunction "CT_4") (pintype "passive"))
    )
    (net (code "231") (name "Net-(U5-A)") (class "Default")
      (node (ref "LED34") (pin "-") (pinfunction "-_-") (pintype "passive"))
      (node (ref "U5") (pin "1") (pinfunction "A_1") (pintype "passive"))
    )
    (net (code "232") (name "Net-(U5-CT)") (class "Default")
      (node (ref "R41") (pin "1") (pinfunction "1_1") (pintype "passive"))
      (node (ref "U5") (pin "4") (pinfunction "CT_4") (pintype "passive"))
    )
    (net (code "233") (name "Net-(U6-A)") (class "Default")
      (node (ref "LED35") (pin "-") (pinfunction "-_-") (pintype "passive"))
      (node (ref "U6") (pin "1") (pinfunction "A_1") (pintype "passive"))
    )
    (net (code "234") (name "Net-(U6-CT)") (class "Default")
      (node (ref "R43") (pin "1") (pinfunction "1_1") (pintype "passive"))
      (node (ref "U6") (pin "4") (pinfunction "CT_4") (pintype "passive"))
    )
    (net (code "235") (name "Net-(U7-A)") (class "Default")
      (node (ref "LED33") (pin "-") (pinfunction "-_-") (pintype "passive"))
      (node (ref "U7") (pin "1") (pinfunction "A_1") (pintype "passive"))
    )
    (net (code "236") (name "Net-(U7-CT)") (class "Default")
      (node (ref "R45") (pin "1") (pinfunction "1_1") (pintype "passive"))
      (node (ref "U7") (pin "4") (pinfunction "CT_4") (pintype "passive"))
    )
    (net (code "237") (name "Net-(U8-A)") (class "Default")
      (node (ref "LED36") (pin "-") (pinfunction "-_-") (pintype "passive"))
      (node (ref "U8") (pin "1") (pinfunction "A_1") (pintype "passive"))
    )
    (net (code "238") (name "Net-(U8-CT)") (class "Default")
      (node (ref "R47") (pin "1") (pinfunction "1_1") (pintype "passive"))
      (node (ref "U8") (pin "4") (pinfunction "CT_4") (pintype "passive"))
    )
    (net (code "239") (name "RS_A") (class "Default")
      (node (ref "JP2") (pin "12") (pinfunction "12_12") (pintype "passive"))
      (node (ref "USB2RS1") (pin "A") (pinfunction "A_A") (pintype "bidirectional"))
    )
    (net (code "240") (name "RS_B") (class "Default")
      (node (ref "JP2") (pin "10") (pinfunction "10_10") (pintype "passive"))
      (node (ref "USB2RS1") (pin "B") (pinfunction "B_B") (pintype "bidirectional"))
    )
    (net (code "241") (name "RX") (class "Default")
      (node (ref "JP2") (pin "3") (pinfunction "3_3") (pintype "passive"))
      (node (ref "TTL-RS1") (pin "RX") (pinfunction "RX_RX") (pintype "bidirectional"))
    )
    (net (code "242") (name "SCL") (class "Default")
      (node (ref "IC1") (pin "12") (pinfunction "SCL_12") (pintype "input"))
      (node (ref "IC4") (pin "12") (pinfunction "SCL_12") (pintype "input"))
      (node (ref "JP2") (pin "9") (pinfunction "9_9") (pintype "passive"))
      (node (ref "R97") (pin "1") (pinfunction "1_1") (pintype "passive"))
      (node (ref "R99") (pin "1") (pinfunction "1_1") (pintype "passive"))
    )
    (net (code "243") (name "SDA") (class "Default")
      (node (ref "IC1") (pin "13") (pinfunction "SDA_13") (pintype "bidirectional"))
      (node (ref "IC4") (pin "13") (pinfunction "SDA_13") (pintype "bidirectional"))
      (node (ref "JP2") (pin "11") (pinfunction "11_11") (pintype "passive"))
      (node (ref "R100") (pin "1") (pinfunction "1_1") (pintype "passive"))
      (node (ref "R98") (pin "1") (pinfunction "1_1") (pintype "passive"))
    )
    (net (code "244") (name "TX") (class "Default")
      (node (ref "JP2") (pin "1") (pinfunction "1_1") (pintype "passive"))
      (node (ref "TTL-RS1") (pin "TX") (pinfunction "TX_TX") (pintype "bidirectional"))
    )
    (net (code "245") (name "USBRS_D+") (class "Default")
      (node (ref "JP2") (pin "8") (pinfunction "8_8") (pintype "passive"))
      (node (ref "USB2RS1") (pin "3") (pinfunction "3_3") (pintype "bidirectional"))
    )
    (net (code "246") (name "USBRS_D-") (class "Default")
      (node (ref "JP2") (pin "6") (pinfunction "6_6") (pintype "passive"))
      (node (ref "USB2RS1") (pin "2") (pinfunction "2_2") (pintype "bidirectional"))
    )
    (net (code "247") (name "VCC") (class "Default")
      (node (ref "D34") (pin "C") (pinfunction "K_C") (pintype "passive"))
      (node (ref "D36") (pin "C") (pinfunction "K_C") (pintype "passive"))
      (node (ref "D38") (pin "C") (pinfunction "K_C") (pintype "passive"))
      (node (ref "D40") (pin "C") (pinfunction "K_C") (pintype "passive"))
      (node (ref "D42") (pin "C") (pinfunction "K_C") (pintype "passive"))
      (node (ref "D44") (pin "C") (pinfunction "K_C") (pintype "passive"))
      (node (ref "D46") (pin "C") (pinfunction "K_C") (pintype "passive"))
      (node (ref "D48") (pin "C") (pinfunction "K_C") (pintype "passive"))
      (node (ref "IC1") (pin "9") (pinfunction "VDD_9") (pintype "power_in"))
      (node (ref "IC4") (pin "9") (pinfunction "VDD_9") (pintype "power_in"))
      (node (ref "JP2") (pin "4") (pinfunction "4_4") (pintype "passive"))
      (node (ref "JP4") (pin "1") (pinfunction "1_1") (pintype "passive"))
      (node (ref "JP4") (pin "3") (pinfunction "3_3") (pintype "passive"))
      (node (ref "K2") (pin "1") (pinfunction "1_1") (pintype "passive"))
      (node (ref "K3") (pin "1") (pinfunction "1_1") (pintype "passive"))
      (node (ref "K4") (pin "1") (pinfunction "1_1") (pintype "passive"))
      (node (ref "K5") (pin "1") (pinfunction "1_1") (pintype "passive"))
      (node (ref "K6") (pin "1") (pinfunction "1_1") (pintype "passive"))
      (node (ref "K7") (pin "1") (pinfunction "1_1") (pintype "passive"))
      (node (ref "K8") (pin "1") (pinfunction "1_1") (pintype "passive"))
      (node (ref "K9") (pin "1") (pinfunction "1_1") (pintype "passive"))
      (node (ref "R100") (pin "2") (pinfunction "2_2") (pintype "passive"))
      (node (ref "R103") (pin "1") (pinfunction "1_1") (pintype "passive"))
      (node (ref "R107") (pin "2") (pinfunction "2_2") (pintype "passive"))
      (node (ref "R108") (pin "1") (pinfunction "1_1") (pintype "passive"))
      (node (ref "R33") (pin "2") (pinfunction "2_2") (pintype "passive"))
      (node (ref "R35") (pin "2") (pinfunction "2_2") (pintype "passive"))
      (node (ref "R37") (pin "2") (pinfunction "2_2") (pintype "passive"))
      (node (ref "R39") (pin "2") (pinfunction "2_2") (pintype "passive"))
      (node (ref "R41") (pin "2") (pinfunction "2_2") (pintype "passive"))
      (node (ref "R43") (pin "2") (pinfunction "2_2") (pintype "passive"))
      (node (ref "R45") (pin "2") (pinfunction "2_2") (pintype "passive"))
      (node (ref "R47") (pin "2") (pinfunction "2_2") (pintype "passive"))
      (node (ref "R49") (pin "2") (pinfunction "2_2") (pintype "passive"))
      (node (ref "R50") (pin "2") (pinfunction "2_2") (pintype "passive"))
      (node (ref "R51") (pin "2") (pinfunction "2_2") (pintype "passive"))
      (node (ref "R52") (pin "2") (pinfunction "2_2") (pintype "passive"))
      (node (ref "R53") (pin "2") (pinfunction "2_2") (pintype "passive"))
      (node (ref "R54") (pin "2") (pinfunction "2_2") (pintype "passive"))
      (node (ref "R55") (pin "2") (pinfunction "2_2") (pintype "passive"))
      (node (ref "R56") (pin "2") (pinfunction "2_2") (pintype "passive"))
      (node (ref "R57") (pin "2") (pinfunction "2_2") (pintype "passive"))
      (node (ref "R58") (pin "2") (pinfunction "2_2") (pintype "passive"))
      (node (ref "R59") (pin "2") (pinfunction "2_2") (pintype "passive"))
      (node (ref "R60") (pin "2") (pinfunction "2_2") (pintype "passive"))
      (node (ref "R61") (pin "2") (pinfunction "2_2") (pintype "passive"))
      (node (ref "R62") (pin "2") (pinfunction "2_2") (pintype "passive"))
      (node (ref "R63") (pin "2") (pinfunction "2_2") (pintype "passive"))
      (node (ref "R64") (pin "2") (pinfunction "2_2") (pintype "passive"))
      (node (ref "R65") (pin "2") (pinfunction "2_2") (pintype "passive"))
      (node (ref "R66") (pin "2") (pinfunction "2_2") (pintype "passive"))
      (node (ref "R67") (pin "2") (pinfunction "2_2") (pintype "passive"))
      (node (ref "R68") (pin "2") (pinfunction "2_2") (pintype "passive"))
      (node (ref "R69") (pin "2") (pinfunction "2_2") (pintype "passive"))
      (node (ref "R70") (pin "2") (pinfunction "2_2") (pintype "passive"))
      (node (ref "R71") (pin "2") (pinfunction "2_2") (pintype "passive"))
      (node (ref "R72") (pin "2") (pinfunction "2_2") (pintype "passive"))
      (node (ref "R73") (pin "2") (pinfunction "2_2") (pintype "passive"))
      (node (ref "R74") (pin "2") (pinfunction "2_2") (pintype "passive"))
      (node (ref "R75") (pin "2") (pinfunction "2_2") (pintype "passive"))
      (node (ref "R76") (pin "2") (pinfunction "2_2") (pintype "passive"))
      (node (ref "R77") (pin "2") (pinfunction "2_2") (pintype "passive"))
      (node (ref "R78") (pin "2") (pinfunction "2_2") (pintype "passive"))
      (node (ref "R79") (pin "2") (pinfunction "2_2") (pintype "passive"))
      (node (ref "R80") (pin "2") (pinfunction "2_2") (pintype "passive"))
      (node (ref "R97") (pin "2") (pinfunction "2_2") (pintype "passive"))
      (node (ref "R98") (pin "2") (pinfunction "2_2") (pintype "passive"))
      (node (ref "R99") (pin "2") (pinfunction "2_2") (pintype "passive"))
      (node (ref "TTL-RS1") (pin "VCC") (pinfunction "VCC_VCC") (pintype "bidirectional"))
      (node (ref "USB2RS1") (pin "1") (pinfunction "1_1") (pintype "bidirectional"))
    )
    (net (code "248") (name "unconnected-(IC1-INTA-Pad20)") (class "Default")
      (node (ref "IC1") (pin "20") (pinfunction "INTA_20") (pintype "output"))
    )
    (net (code "249") (name "unconnected-(IC1-INTB-Pad19)") (class "Default")
      (node (ref "IC1") (pin "19") (pinfunction "INTB_19") (pintype "output"))
    )
    (net (code "250") (name "unconnected-(IC4-INTA-Pad20)") (class "Default")
      (node (ref "IC4") (pin "20") (pinfunction "INTA_20") (pintype "output"))
    )
    (net (code "251") (name "unconnected-(IC4-INTB-Pad19)") (class "Default")
      (node (ref "IC4") (pin "19") (pinfunction "INTB_19") (pintype "output"))
    )
    (net (code "252") (name "unconnected-(K2B-O-PadO1)") (class "Default")
      (node (ref "K2") (pin "O1") (pinfunction "O_O1") (pintype "passive"))
    )
    (net (code "253") (name "unconnected-(K2C-O-PadO2)") (class "Default")
      (node (ref "K2") (pin "O2") (pinfunction "O_O2") (pintype "passive"))
    )
    (net (code "254") (name "unconnected-(K2C-P-PadP2)") (class "Default")
      (node (ref "K2") (pin "P2") (pinfunction "P_P2") (pintype "passive"))
    )
    (net (code "255") (name "unconnected-(K2C-S-PadS2)") (class "Default")
      (node (ref "K2") (pin "S2") (pinfunction "S_S2") (pintype "passive"))
    )
    (net (code "256") (name "unconnected-(K3B-O-PadO1)") (class "Default")
      (node (ref "K3") (pin "O1") (pinfunction "O_O1") (pintype "passive"))
    )
    (net (code "257") (name "unconnected-(K3C-O-PadO2)") (class "Default")
      (node (ref "K3") (pin "O2") (pinfunction "O_O2") (pintype "passive"))
    )
    (net (code "258") (name "unconnected-(K3C-P-PadP2)") (class "Default")
      (node (ref "K3") (pin "P2") (pinfunction "P_P2") (pintype "passive"))
    )
    (net (code "259") (name "unconnected-(K3C-S-PadS2)") (class "Default")
      (node (ref "K3") (pin "S2") (pinfunction "S_S2") (pintype "passive"))
    )
    (net (code "260") (name "unconnected-(K4B-O-PadO1)") (class "Default")
      (node (ref "K4") (pin "O1") (pinfunction "O_O1") (pintype "passive"))
    )
    (net (code "261") (name "unconnected-(K4C-O-PadO2)") (class "Default")
      (node (ref "K4") (pin "O2") (pinfunction "O_O2") (pintype "passive"))
    )
    (net (code "262") (name "unconnected-(K4C-P-PadP2)") (class "Default")
      (node (ref "K4") (pin "P2") (pinfunction "P_P2") (pintype "passive"))
    )
    (net (code "263") (name "unconnected-(K4C-S-PadS2)") (class "Default")
      (node (ref "K4") (pin "S2") (pinfunction "S_S2") (pintype "passive"))
    )
    (net (code "264") (name "unconnected-(K5B-O-PadO1)") (class "Default")
      (node (ref "K5") (pin "O1") (pinfunction "O_O1") (pintype "passive"))
    )
    (net (code "265") (name "unconnected-(K5C-O-PadO2)") (class "Default")
      (node (ref "K5") (pin "O2") (pinfunction "O_O2") (pintype "passive"))
    )
    (net (code "266") (name "unconnected-(K5C-P-PadP2)") (class "Default")
      (node (ref "K5") (pin "P2") (pinfunction "P_P2") (pintype "passive"))
    )
    (net (code "267") (name "unconnected-(K5C-S-PadS2)") (class "Default")
      (node (ref "K5") (pin "S2") (pinfunction "S_S2") (pintype "passive"))
    )
    (net (code "268") (name "unconnected-(K6B-O-PadO1)") (class "Default")
      (node (ref "K6") (pin "O1") (pinfunction "O_O1") (pintype "passive"))
    )
    (net (code "269") (name "unconnected-(K6C-O-PadO2)") (class "Default")
      (node (ref "K6") (pin "O2") (pinfunction "O_O2") (pintype "passive"))
    )
    (net (code "270") (name "unconnected-(K6C-P-PadP2)") (class "Default")
      (node (ref "K6") (pin "P2") (pinfunction "P_P2") (pintype "passive"))
    )
    (net (code "271") (name "unconnected-(K6C-S-PadS2)") (class "Default")
      (node (ref "K6") (pin "S2") (pinfunction "S_S2") (pintype "passive"))
    )
    (net (code "272") (name "unconnected-(K7B-O-PadO1)") (class "Default")
      (node (ref "K7") (pin "O1") (pinfunction "O_O1") (pintype "passive"))
    )
    (net (code "273") (name "unconnected-(K7C-O-PadO2)") (class "Default")
      (node (ref "K7") (pin "O2") (pinfunction "O_O2") (pintype "passive"))
    )
    (net (code "274") (name "unconnected-(K7C-P-PadP2)") (class "Default")
      (node (ref "K7") (pin "P2") (pinfunction "P_P2") (pintype "passive"))
    )
    (net (code "275") (name "unconnected-(K7C-S-PadS2)") (class "Default")
      (node (ref "K7") (pin "S2") (pinfunction "S_S2") (pintype "passive"))
    )
    (net (code "276") (name "unconnected-(K8B-O-PadO1)") (class "Default")
      (node (ref "K8") (pin "O1") (pinfunction "O_O1") (pintype "passive"))
    )
    (net (code "277") (name "unconnected-(K8C-O-PadO2)") (class "Default")
      (node (ref "K8") (pin "O2") (pinfunction "O_O2") (pintype "passive"))
    )
    (net (code "278") (name "unconnected-(K8C-P-PadP2)") (class "Default")
      (node (ref "K8") (pin "P2") (pinfunction "P_P2") (pintype "passive"))
    )
    (net (code "279") (name "unconnected-(K8C-S-PadS2)") (class "Default")
      (node (ref "K8") (pin "S2") (pinfunction "S_S2") (pintype "passive"))
    )
    (net (code "280") (name "unconnected-(K9B-O-PadO1)") (class "Default")
      (node (ref "K9") (pin "O1") (pinfunction "O_O1") (pintype "passive"))
    )
    (net (code "281") (name "unconnected-(K9C-O-PadO2)") (class "Default")
      (node (ref "K9") (pin "O2") (pinfunction "O_O2") (pintype "passive"))
    )
    (net (code "282") (name "unconnected-(K9C-P-PadP2)") (class "Default")
      (node (ref "K9") (pin "P2") (pinfunction "P_P2") (pintype "passive"))
    )
    (net (code "283") (name "unconnected-(K9C-S-PadS2)") (class "Default")
      (node (ref "K9") (pin "S2") (pinfunction "S_S2") (pintype "passive"))
    )
  )
)
